# robot_board.net
KiCad netlist of a schematic drawn in EAGLE
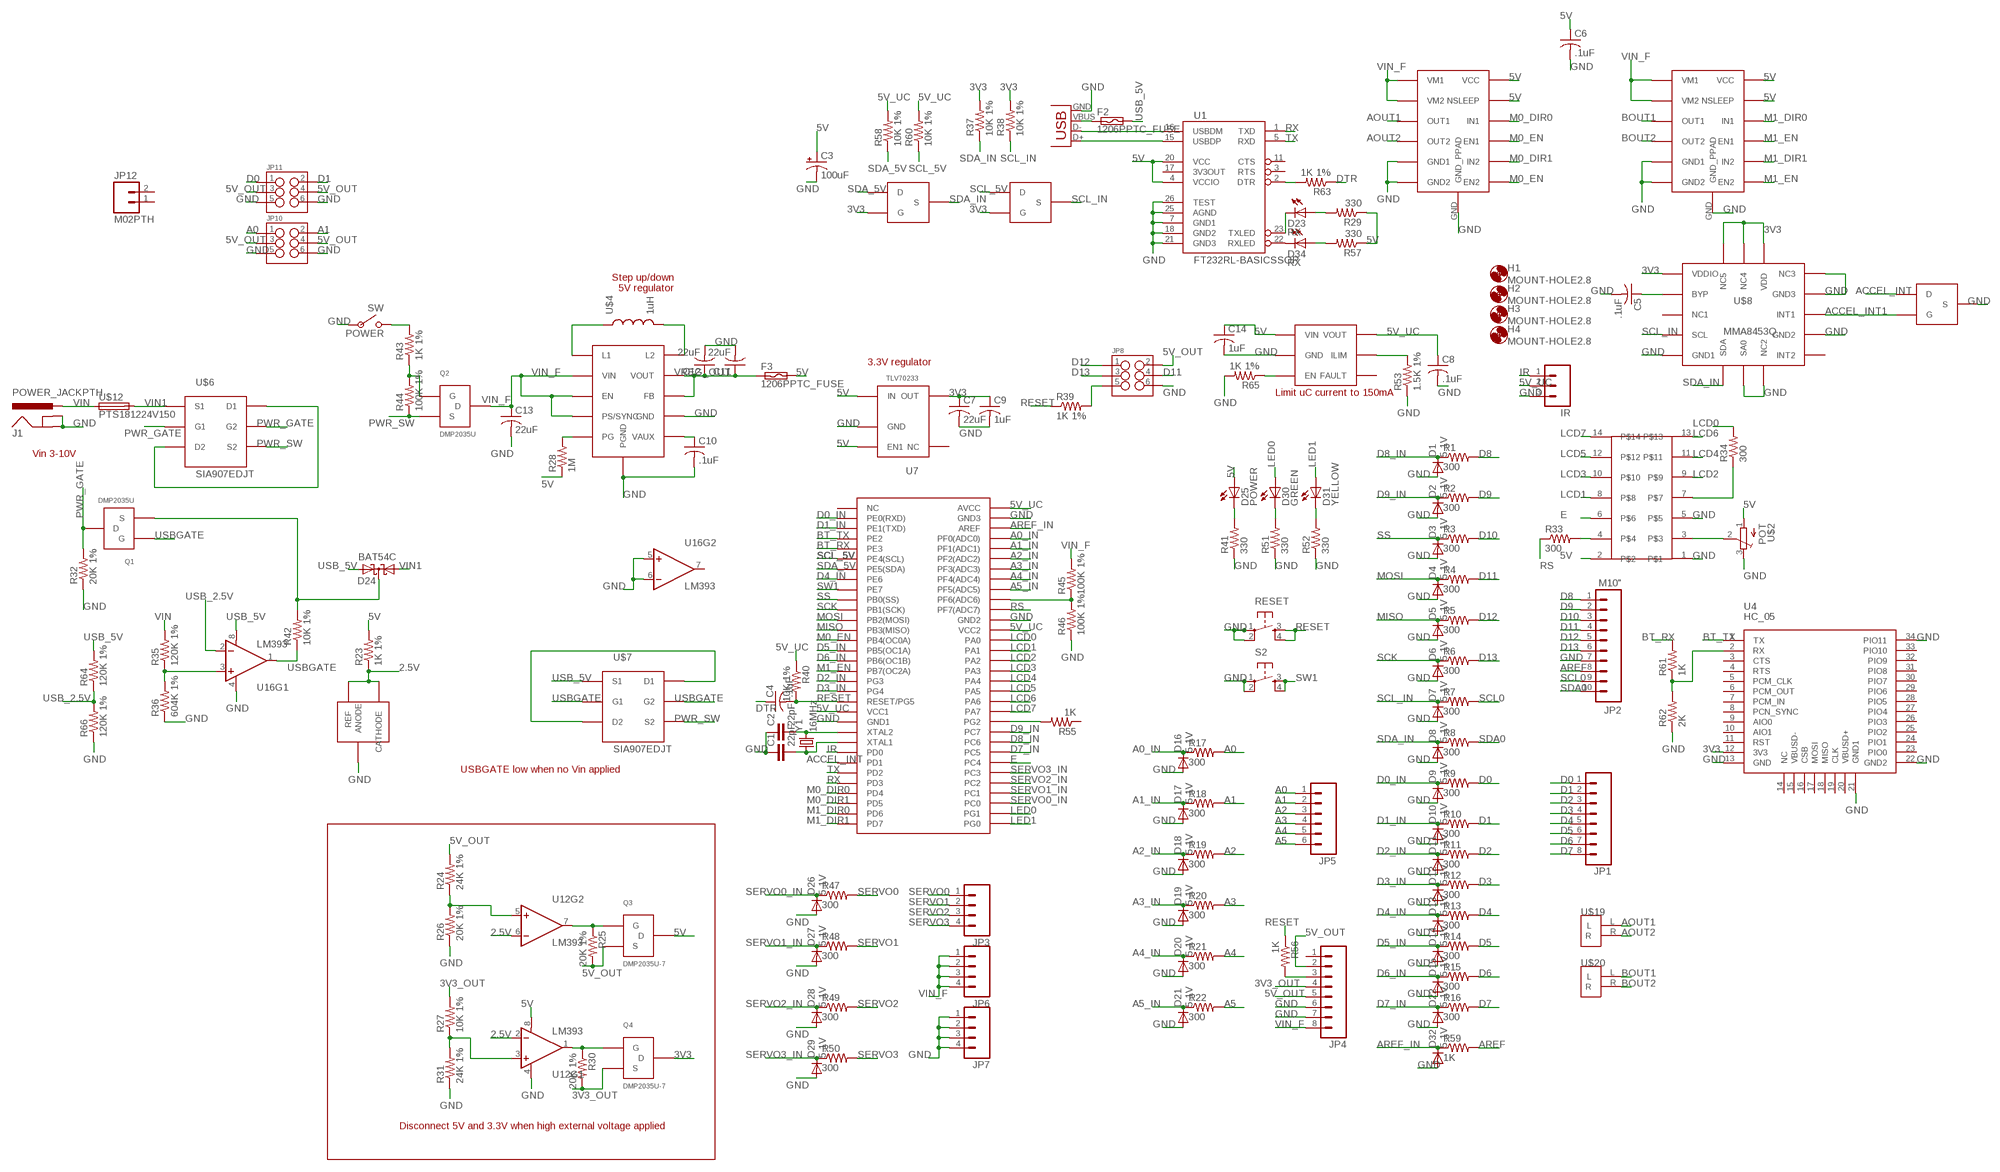
[diagram p0: schematic, sheet 1]

(export (version "E")
  (design (tool "Eeschema 10.0.6"))
  (components
    (comp (ref "C1")
      (value "22pF")
      (footprint "eagle-import:0805")
      (libsource (lib "eagle-import") (part "CAP0805"))
    )
    (comp (ref "C2")
      (value "22pF")
      (footprint "eagle-import:0805")
      (libsource (lib "eagle-import") (part "CAP0805"))
    )
    (comp (ref "C3")
      (value "100uF")
      (footprint "eagle-import:PANASONIC_D")
      (libsource (lib "eagle-import") (part "CAP_POLD"))
    )
    (comp (ref "C4")
      (value ".1uF")
      (footprint "eagle-import:C1206")
      (libsource (lib "eagle-import") (part "C-USC1206"))
    )
    (comp (ref "C5")
      (value ".1uF")
      (footprint "eagle-import:C1206")
      (libsource (lib "eagle-import") (part "C-USC1206"))
    )
    (comp (ref "C6")
      (value ".1uF")
      (footprint "eagle-import:C1206")
      (libsource (lib "eagle-import") (part "C-USC1206"))
    )
    (comp (ref "C7")
      (value "22uF")
      (footprint "eagle-import:C1206")
      (libsource (lib "eagle-import") (part "C-USC1206"))
    )
    (comp (ref "C8")
      (value ".1uF")
      (footprint "eagle-import:C1206")
      (libsource (lib "eagle-import") (part "C-USC1206"))
    )
    (comp (ref "C9")
      (value "1uF")
      (footprint "eagle-import:C1206")
      (libsource (lib "eagle-import") (part "C-USC1206"))
    )
    (comp (ref "C10")
      (value ".1uF")
      (footprint "eagle-import:C1206")
      (libsource (lib "eagle-import") (part "C-USC1206"))
    )
    (comp (ref "C11")
      (value "22uF")
      (footprint "eagle-import:C1206")
      (libsource (lib "eagle-import") (part "C-USC1206"))
    )
    (comp (ref "C12")
      (value "22uF")
      (footprint "eagle-import:C1206")
      (libsource (lib "eagle-import") (part "C-USC1206"))
    )
    (comp (ref "C13")
      (value "22uF")
      (footprint "eagle-import:C1206")
      (libsource (lib "eagle-import") (part "C-USC1206"))
    )
    (comp (ref "C14")
      (value "1uF")
      (footprint "eagle-import:C1206")
      (libsource (lib "eagle-import") (part "C-USC1206"))
    )
    (comp (ref "D1")
      (value "5.1V")
      (footprint "eagle-import:SOT23-3")
      (libsource (lib "eagle-import") (part "DIODESOT23"))
    )
    (comp (ref "D2")
      (value "5.1V")
      (footprint "eagle-import:SOT23-3")
      (libsource (lib "eagle-import") (part "DIODESOT23"))
    )
    (comp (ref "D3")
      (value "5.1V")
      (footprint "eagle-import:SOT23-3")
      (libsource (lib "eagle-import") (part "DIODESOT23"))
    )
    (comp (ref "D4")
      (value "5.1V")
      (footprint "eagle-import:SOT23-3")
      (libsource (lib "eagle-import") (part "DIODESOT23"))
    )
    (comp (ref "D5")
      (value "5.1V")
      (footprint "eagle-import:SOT23-3")
      (libsource (lib "eagle-import") (part "DIODESOT23"))
    )
    (comp (ref "D6")
      (value "5.1V")
      (footprint "eagle-import:SOT23-3")
      (libsource (lib "eagle-import") (part "DIODESOT23"))
    )
    (comp (ref "D7")
      (value "5.1V")
      (footprint "eagle-import:SOT23-3")
      (libsource (lib "eagle-import") (part "DIODESOT23"))
    )
    (comp (ref "D8")
      (value "5.1V")
      (footprint "eagle-import:SOT23-3")
      (libsource (lib "eagle-import") (part "DIODESOT23"))
    )
    (comp (ref "D9")
      (value "5.1V")
      (footprint "eagle-import:SOT23-3")
      (libsource (lib "eagle-import") (part "DIODESOT23"))
    )
    (comp (ref "D10")
      (value "5.1V")
      (footprint "eagle-import:SOT23-3")
      (libsource (lib "eagle-import") (part "DIODESOT23"))
    )
    (comp (ref "D11")
      (value "5.1V")
      (footprint "eagle-import:SOT23-3")
      (libsource (lib "eagle-import") (part "DIODESOT23"))
    )
    (comp (ref "D12")
      (value "5.1V")
      (footprint "eagle-import:SOT23-3")
      (libsource (lib "eagle-import") (part "DIODESOT23"))
    )
    (comp (ref "D13")
      (value "5.1V")
      (footprint "eagle-import:SOT23-3")
      (libsource (lib "eagle-import") (part "DIODESOT23"))
    )
    (comp (ref "D14")
      (value "5.1V")
      (footprint "eagle-import:SOT23-3")
      (libsource (lib "eagle-import") (part "DIODESOT23"))
    )
    (comp (ref "D15")
      (value "5.1V")
      (footprint "eagle-import:SOT23-3")
      (libsource (lib "eagle-import") (part "DIODESOT23"))
    )
    (comp (ref "D16")
      (value "5.1V")
      (footprint "eagle-import:SOT23-3")
      (libsource (lib "eagle-import") (part "DIODESOT23"))
    )
    (comp (ref "D17")
      (value "5.1V")
      (footprint "eagle-import:SOT23-3")
      (libsource (lib "eagle-import") (part "DIODESOT23"))
    )
    (comp (ref "D18")
      (value "5.1V")
      (footprint "eagle-import:SOT23-3")
      (libsource (lib "eagle-import") (part "DIODESOT23"))
    )
    (comp (ref "D19")
      (value "5.1V")
      (footprint "eagle-import:SOT23-3")
      (libsource (lib "eagle-import") (part "DIODESOT23"))
    )
    (comp (ref "D20")
      (value "5.1V")
      (footprint "eagle-import:SOT23-3")
      (libsource (lib "eagle-import") (part "DIODESOT23"))
    )
    (comp (ref "D21")
      (value "5.1V")
      (footprint "eagle-import:SOT23-3")
      (libsource (lib "eagle-import") (part "DIODESOT23"))
    )
    (comp (ref "D22")
      (value "5.1V")
      (footprint "eagle-import:SOT23-3")
      (libsource (lib "eagle-import") (part "DIODESOT23"))
    )
    (comp (ref "D23")
      (value "RX")
      (footprint "eagle-import:LED-1206")
      (libsource (lib "eagle-import") (part "LED-GREENLILYPAD"))
    )
    (comp (ref "D24")
      (value "BAT54C")
      (footprint "eagle-import:SOT23")
      (libsource (lib "eagle-import") (part "BAT54C"))
    )
    (comp (ref "D25")
      (value "POWER")
      (footprint "eagle-import:LED-1206")
      (libsource (lib "eagle-import") (part "LED-GREENLILYPAD"))
    )
    (comp (ref "D26")
      (value "5.1V")
      (footprint "eagle-import:SOT23-3")
      (libsource (lib "eagle-import") (part "DIODESOT23"))
    )
    (comp (ref "D27")
      (value "5.1V")
      (footprint "eagle-import:SOT23-3")
      (libsource (lib "eagle-import") (part "DIODESOT23"))
    )
    (comp (ref "D28")
      (value "5.1V")
      (footprint "eagle-import:SOT23-3")
      (libsource (lib "eagle-import") (part "DIODESOT23"))
    )
    (comp (ref "D29")
      (value "5.1V")
      (footprint "eagle-import:SOT23-3")
      (libsource (lib "eagle-import") (part "DIODESOT23"))
    )
    (comp (ref "D30")
      (value "GREEN")
      (footprint "eagle-import:LED-1206")
      (libsource (lib "eagle-import") (part "LED-GREENLILYPAD"))
    )
    (comp (ref "D31")
      (value "YELLOW")
      (footprint "eagle-import:LED-1206")
      (libsource (lib "eagle-import") (part "LED-GREENLILYPAD"))
    )
    (comp (ref "D32")
      (value "5.1V")
      (footprint "eagle-import:SOT23-3")
      (libsource (lib "eagle-import") (part "DIODESOT23"))
    )
    (comp (ref "D34")
      (value "RX")
      (footprint "eagle-import:LED-1206")
      (libsource (lib "eagle-import") (part "LED-GREENLILYPAD"))
    )
    (comp (ref "F2")
      (value "1206PPTC_FUSE")
      (footprint "eagle-import:R1206")
      (libsource (lib "eagle-import") (part "1206PPTC_FUSE"))
    )
    (comp (ref "F3")
      (value "1206PPTC_FUSE")
      (footprint "eagle-import:R1206")
      (libsource (lib "eagle-import") (part "1206PPTC_FUSE"))
    )
    (comp (ref "H1")
      (value "MOUNT-HOLE2.8")
      (footprint "eagle-import:2,8")
      (libsource (lib "eagle-import") (part "MOUNT-HOLE2.8"))
    )
    (comp (ref "H2")
      (value "MOUNT-HOLE2.8")
      (footprint "eagle-import:2,8")
      (libsource (lib "eagle-import") (part "MOUNT-HOLE2.8"))
    )
    (comp (ref "H3")
      (value "MOUNT-HOLE2.8")
      (footprint "eagle-import:2,8")
      (libsource (lib "eagle-import") (part "MOUNT-HOLE2.8"))
    )
    (comp (ref "H4")
      (value "MOUNT-HOLE2.8")
      (footprint "eagle-import:2,8")
      (libsource (lib "eagle-import") (part "MOUNT-HOLE2.8"))
    )
    (comp (ref "IR")
      (value "M03PTH")
      (footprint "eagle-import:1X03")
      (libsource (lib "eagle-import") (part "M03PTH"))
    )
    (comp (ref "J1")
      (value "POWER_JACKPTH")
      (footprint "eagle-import:POWER_JACK_PTH")
      (libsource (lib "eagle-import") (part "POWER_JACKPTH"))
    )
    (comp (ref "JP1")
      (value "M081X08")
      (footprint "eagle-import:1X08")
      (libsource (lib "eagle-import") (part "M081X08"))
    )
    (comp (ref "JP2")
      (value "M10\"")
      (footprint "eagle-import:1X10")
      (libsource (lib "eagle-import") (part "M10{dblquote}"))
    )
    (comp (ref "JP3")
      (value "M04PTH")
      (footprint "eagle-import:1X04")
      (libsource (lib "eagle-import") (part "M04PTH"))
    )
    (comp (ref "JP4")
      (value "M081X08")
      (footprint "eagle-import:1X08")
      (libsource (lib "eagle-import") (part "M081X08"))
    )
    (comp (ref "JP5")
      (value "M06SIP")
      (footprint "eagle-import:1X06")
      (libsource (lib "eagle-import") (part "M06SIP"))
    )
    (comp (ref "JP6")
      (value "M04PTH")
      (footprint "eagle-import:1X04")
      (libsource (lib "eagle-import") (part "M04PTH"))
    )
    (comp (ref "JP7")
      (value "M04PTH")
      (footprint "eagle-import:1X04")
      (libsource (lib "eagle-import") (part "M04PTH"))
    )
    (comp (ref "JP8")
      (value "M03X22X3_SILK_SM")
      (footprint "eagle-import:2X3")
      (libsource (lib "eagle-import") (part "M03X22X3_SILK_SM"))
    )
    (comp (ref "JP9")
      (value "USB-B")
      (footprint "eagle-import:USB-B-PTH")
      (libsource (lib "eagle-import") (part "USBPTH"))
    )
    (comp (ref "JP10")
      (value "M03X22X3_SILK_SM")
      (footprint "eagle-import:2X3")
      (libsource (lib "eagle-import") (part "M03X22X3_SILK_SM"))
    )
    (comp (ref "JP11")
      (value "M03X22X3_SILK_SM")
      (footprint "eagle-import:2X3")
      (libsource (lib "eagle-import") (part "M03X22X3_SILK_SM"))
    )
    (comp (ref "JP12")
      (value "M02PTH")
      (footprint "eagle-import:1X02")
      (libsource (lib "eagle-import") (part "M02PTH"))
    )
    (comp (ref "POWER")
      (value "SW")
      (footprint "eagle-import:SW")
      (libsource (lib "eagle-import") (part "SW"))
    )
    (comp (ref "Q1")
      (value "DMP2035U")
      (footprint "eagle-import:SOT23")
      (libsource (lib "eagle-import") (part "DMP2035U"))
    )
    (comp (ref "Q2")
      (value "DMP2035U")
      (footprint "eagle-import:SOT23")
      (libsource (lib "eagle-import") (part "DMP2035U"))
    )
    (comp (ref "Q3")
      (value "DMP2035U-7")
      (footprint "eagle-import:SOT23@1")
      (libsource (lib "eagle-import") (part "DMP2035U-7"))
    )
    (comp (ref "Q4")
      (value "DMP2035U-7")
      (footprint "eagle-import:SOT23@1")
      (libsource (lib "eagle-import") (part "DMP2035U-7"))
    )
    (comp (ref "R1")
      (value "300")
      (footprint "eagle-import:R1206")
      (libsource (lib "eagle-import") (part "R-US_R1206"))
    )
    (comp (ref "R2")
      (value "300")
      (footprint "eagle-import:R1206")
      (libsource (lib "eagle-import") (part "R-US_R1206"))
    )
    (comp (ref "R3")
      (value "300")
      (footprint "eagle-import:R1206")
      (libsource (lib "eagle-import") (part "R-US_R1206"))
    )
    (comp (ref "R4")
      (value "300")
      (footprint "eagle-import:R1206")
      (libsource (lib "eagle-import") (part "R-US_R1206"))
    )
    (comp (ref "R5")
      (value "300")
      (footprint "eagle-import:R1206")
      (libsource (lib "eagle-import") (part "R-US_R1206"))
    )
    (comp (ref "R6")
      (value "300")
      (footprint "eagle-import:R1206")
      (libsource (lib "eagle-import") (part "R-US_R1206"))
    )
    (comp (ref "R7")
      (value "300")
      (footprint "eagle-import:R1206")
      (libsource (lib "eagle-import") (part "R-US_R1206"))
    )
    (comp (ref "R8")
      (value "300")
      (footprint "eagle-import:R1206")
      (libsource (lib "eagle-import") (part "R-US_R1206"))
    )
    (comp (ref "R9")
      (value "300")
      (footprint "eagle-import:R1206")
      (libsource (lib "eagle-import") (part "R-US_R1206"))
    )
    (comp (ref "R10")
      (value "300")
      (footprint "eagle-import:R1206")
      (libsource (lib "eagle-import") (part "R-US_R1206"))
    )
    (comp (ref "R11")
      (value "300")
      (footprint "eagle-import:R1206")
      (libsource (lib "eagle-import") (part "R-US_R1206"))
    )
    (comp (ref "R12")
      (value "300")
      (footprint "eagle-import:R1206")
      (libsource (lib "eagle-import") (part "R-US_R1206"))
    )
    (comp (ref "R13")
      (value "300")
      (footprint "eagle-import:R1206")
      (libsource (lib "eagle-import") (part "R-US_R1206"))
    )
    (comp (ref "R14")
      (value "300")
      (footprint "eagle-import:R1206")
      (libsource (lib "eagle-import") (part "R-US_R1206"))
    )
    (comp (ref "R15")
      (value "300")
      (footprint "eagle-import:R1206")
      (libsource (lib "eagle-import") (part "R-US_R1206"))
    )
    (comp (ref "R16")
      (value "300")
      (footprint "eagle-import:R1206")
      (libsource (lib "eagle-import") (part "R-US_R1206"))
    )
    (comp (ref "R17")
      (value "300")
      (footprint "eagle-import:R1206")
      (libsource (lib "eagle-import") (part "R-US_R1206"))
    )
    (comp (ref "R18")
      (value "300")
      (footprint "eagle-import:R1206")
      (libsource (lib "eagle-import") (part "R-US_R1206"))
    )
    (comp (ref "R19")
      (value "300")
      (footprint "eagle-import:R1206")
      (libsource (lib "eagle-import") (part "R-US_R1206"))
    )
    (comp (ref "R20")
      (value "300")
      (footprint "eagle-import:R1206")
      (libsource (lib "eagle-import") (part "R-US_R1206"))
    )
    (comp (ref "R21")
      (value "300")
      (footprint "eagle-import:R1206")
      (libsource (lib "eagle-import") (part "R-US_R1206"))
    )
    (comp (ref "R22")
      (value "300")
      (footprint "eagle-import:R1206")
      (libsource (lib "eagle-import") (part "R-US_R1206"))
    )
    (comp (ref "R23")
      (value "1K 1%")
      (footprint "eagle-import:R1206")
      (libsource (lib "eagle-import") (part "R-US_R1206"))
    )
    (comp (ref "R24")
      (value "24K 1%")
      (footprint "eagle-import:R1206")
      (libsource (lib "eagle-import") (part "R-US_R1206"))
    )
    (comp (ref "R25")
      (value "20K 1%")
      (footprint "eagle-import:R1206")
      (libsource (lib "eagle-import") (part "R-US_R1206"))
    )
    (comp (ref "R26")
      (value "20K 1%")
      (footprint "eagle-import:R1206")
      (libsource (lib "eagle-import") (part "R-US_R1206"))
    )
    (comp (ref "R27")
      (value "10K 1%")
      (footprint "eagle-import:R1206")
      (libsource (lib "eagle-import") (part "R-US_R1206"))
    )
    (comp (ref "R28")
      (value "1M")
      (footprint "eagle-import:R1206")
      (libsource (lib "eagle-import") (part "R-US_R1206"))
    )
    (comp (ref "R29")
      (value "330")
      (footprint "eagle-import:R1206")
      (libsource (lib "eagle-import") (part "R-US_R1206"))
    )
    (comp (ref "R30")
      (value "20K 1%")
      (footprint "eagle-import:R1206")
      (libsource (lib "eagle-import") (part "R-US_R1206"))
    )
    (comp (ref "R31")
      (value "24K 1%")
      (footprint "eagle-import:R1206")
      (libsource (lib "eagle-import") (part "R-US_R1206"))
    )
    (comp (ref "R32")
      (value "20K 1%")
      (footprint "eagle-import:R1206")
      (libsource (lib "eagle-import") (part "R-US_R1206"))
    )
    (comp (ref "R33")
      (value "300")
      (footprint "eagle-import:R1206")
      (libsource (lib "eagle-import") (part "R-US_R1206"))
    )
    (comp (ref "R34")
      (value "300")
      (footprint "eagle-import:R1206")
      (libsource (lib "eagle-import") (part "R-US_R1206"))
    )
    (comp (ref "R35")
      (value "120K 1%")
      (footprint "eagle-import:R1206")
      (libsource (lib "eagle-import") (part "R-US_R1206"))
    )
    (comp (ref "R36")
      (value "604K 1%")
      (footprint "eagle-import:R1206")
      (libsource (lib "eagle-import") (part "R-US_R1206"))
    )
    (comp (ref "R37")
      (value "10K 1%")
      (footprint "eagle-import:R1206")
      (libsource (lib "eagle-import") (part "R-US_R1206"))
    )
    (comp (ref "R38")
      (value "10K 1%")
      (footprint "eagle-import:R1206")
      (libsource (lib "eagle-import") (part "R-US_R1206"))
    )
    (comp (ref "R39")
      (value "1K 1%")
      (footprint "eagle-import:R1206")
      (libsource (lib "eagle-import") (part "R-US_R1206"))
    )
    (comp (ref "R40")
      (value "10K 1%")
      (footprint "eagle-import:R1206")
      (libsource (lib "eagle-import") (part "R-US_R1206"))
    )
    (comp (ref "R41")
      (value "330")
      (footprint "eagle-import:R1206")
      (libsource (lib "eagle-import") (part "R-US_R1206"))
    )
    (comp (ref "R42")
      (value "10K 1%")
      (footprint "eagle-import:R1206")
      (libsource (lib "eagle-import") (part "R-US_R1206"))
    )
    (comp (ref "R43")
      (value "1K 1%")
      (footprint "eagle-import:R1206")
      (libsource (lib "eagle-import") (part "R-US_R1206"))
    )
    (comp (ref "R44")
      (value "100K 1%")
      (footprint "eagle-import:R1206")
      (libsource (lib "eagle-import") (part "R-US_R1206"))
    )
    (comp (ref "R45")
      (value "100K 1%")
      (footprint "eagle-import:R1206")
      (libsource (lib "eagle-import") (part "R-US_R1206"))
    )
    (comp (ref "R46")
      (value "100K 1%")
      (footprint "eagle-import:R1206")
      (libsource (lib "eagle-import") (part "R-US_R1206"))
    )
    (comp (ref "R47")
      (value "300")
      (footprint "eagle-import:R1206")
      (libsource (lib "eagle-import") (part "R-US_R1206"))
    )
    (comp (ref "R48")
      (value "300")
      (footprint "eagle-import:R1206")
      (libsource (lib "eagle-import") (part "R-US_R1206"))
    )
    (comp (ref "R49")
      (value "300")
      (footprint "eagle-import:R1206")
      (libsource (lib "eagle-import") (part "R-US_R1206"))
    )
    (comp (ref "R50")
      (value "300")
      (footprint "eagle-import:R1206")
      (libsource (lib "eagle-import") (part "R-US_R1206"))
    )
    (comp (ref "R51")
      (value "330")
      (footprint "eagle-import:R1206")
      (libsource (lib "eagle-import") (part "R-US_R1206"))
    )
    (comp (ref "R52")
      (value "330")
      (footprint "eagle-import:R1206")
      (libsource (lib "eagle-import") (part "R-US_R1206"))
    )
    (comp (ref "R53")
      (value "1.5K 1%")
      (footprint "eagle-import:R1206")
      (libsource (lib "eagle-import") (part "R-US_R1206"))
    )
    (comp (ref "R55")
      (value "1K")
      (footprint "eagle-import:R1206")
      (libsource (lib "eagle-import") (part "R-US_R1206"))
    )
    (comp (ref "R56")
      (value "1K")
      (footprint "eagle-import:R1206")
      (libsource (lib "eagle-import") (part "R-US_R1206"))
    )
    (comp (ref "R57")
      (value "330")
      (footprint "eagle-import:R1206")
      (libsource (lib "eagle-import") (part "R-US_R1206"))
    )
    (comp (ref "R58")
      (value "10K 1%")
      (footprint "eagle-import:R1206")
      (libsource (lib "eagle-import") (part "R-US_R1206"))
    )
    (comp (ref "R59")
      (value "1K")
      (footprint "eagle-import:R1206")
      (libsource (lib "eagle-import") (part "R-US_R1206"))
    )
    (comp (ref "R60")
      (value "10K 1%")
      (footprint "eagle-import:R1206")
      (libsource (lib "eagle-import") (part "R-US_R1206"))
    )
    (comp (ref "R61")
      (value "1K")
      (footprint "eagle-import:R1206")
      (libsource (lib "eagle-import") (part "R-US_R1206"))
    )
    (comp (ref "R62")
      (value "2K")
      (footprint "eagle-import:R1206")
      (libsource (lib "eagle-import") (part "R-US_R1206"))
    )
    (comp (ref "R63")
      (value "1K 1%")
      (footprint "eagle-import:R1206")
      (libsource (lib "eagle-import") (part "R-US_R1206"))
    )
    (comp (ref "R64")
      (value "120K 1%")
      (footprint "eagle-import:R1206")
      (libsource (lib "eagle-import") (part "R-US_R1206"))
    )
    (comp (ref "R65")
      (value "1K 1%")
      (footprint "eagle-import:R1206")
      (libsource (lib "eagle-import") (part "R-US_R1206"))
    )
    (comp (ref "R66")
      (value "120K 1%")
      (footprint "eagle-import:R1206")
      (libsource (lib "eagle-import") (part "R-US_R1206"))
    )
    (comp (ref "RESET")
      (value "TAC_SWITCHPTH")
      (footprint "eagle-import:TACTILE-PTH")
      (libsource (lib "eagle-import") (part "TAC_SWITCHPTH"))
    )
    (comp (ref "S2")
      (value "TAC_SWITCHPTH")
      (footprint "eagle-import:TACTILE-PTH")
      (libsource (lib "eagle-import") (part "TAC_SWITCHPTH"))
    )
    (comp (ref "U$1")
      (value "2X7HEADER")
      (footprint "eagle-import:2X7")
      (libsource (lib "eagle-import") (part "2X7HEADER"))
    )
    (comp (ref "U$2")
      (value "POT")
      (footprint "eagle-import:POT")
      (libsource (lib "eagle-import") (part "POT"))
    )
    (comp (ref "U$3")
      (value "TPS63061")
      (footprint "eagle-import:WSON-10")
      (libsource (lib "eagle-import") (part "TPS63061"))
    )
    (comp (ref "U$4")
      (value "1uH")
      (footprint "eagle-import:TAIYO4012")
      (libsource (lib "eagle-import") (part "TAIYO4012"))
    )
    (comp (ref "U$5")
      (value "AP431SAG-7")
      (footprint "eagle-import:SOT23")
      (libsource (lib "eagle-import") (part "AP431SAG-7"))
    )
    (comp (ref "U$6")
      (value "SIA907EDJT")
      (footprint "eagle-import:SC70T")
      (libsource (lib "eagle-import") (part "SIA907EDJT"))
    )
    (comp (ref "U$7")
      (value "SIA907EDJT")
      (footprint "eagle-import:SC70T")
      (libsource (lib "eagle-import") (part "SIA907EDJT"))
    )
    (comp (ref "U$8")
      (value "MMA8453Q")
      (footprint "eagle-import:QFN-COL")
      (libsource (lib "eagle-import") (part "MMA8453Q"))
    )
    (comp (ref "U$9")
      (value "BSS138")
      (footprint "eagle-import:SOT23")
      (libsource (lib "eagle-import") (part "BSS138"))
    )
    (comp (ref "U$10")
      (value "BSS138")
      (footprint "eagle-import:SOT23")
      (libsource (lib "eagle-import") (part "BSS138"))
    )
    (comp (ref "U$11")
      (value "BSS138")
      (footprint "eagle-import:SOT23")
      (libsource (lib "eagle-import") (part "BSS138"))
    )
    (comp (ref "U$12")
      (value "PTS181224V150")
      (footprint "eagle-import:C1812")
      (libsource (lib "eagle-import") (part "PTS181224V150"))
    )
    (comp (ref "U$19")
      (value "2POS_TERMINAL")
      (footprint "eagle-import:2POS_TERMINAL")
      (libsource (lib "eagle-import") (part "2POS_TERMINAL"))
    )
    (comp (ref "U$20")
      (value "2POS_TERMINAL")
      (footprint "eagle-import:2POS_TERMINAL")
      (libsource (lib "eagle-import") (part "2POS_TERMINAL"))
    )
    (comp (ref "U1")
      (value "FT232RL-BASICSSOP")
      (footprint "eagle-import:SSOP28DB")
      (libsource (lib "eagle-import") (part "FT232RL-BASICSSOP"))
    )
    (comp (ref "U4")
      (value "HC_05")
      (footprint "eagle-import:BLUETOOTH_SMD")
      (libsource (lib "eagle-import") (part "HC_05"))
    )
    (comp (ref "U7")
      (value "TLV70233")
      (footprint "eagle-import:SOT-23-5")
      (libsource (lib "eagle-import") (part "TLV70233"))
    )
    (comp (ref "U8")
      (value "MIC2009A")
      (footprint "eagle-import:SOT23-M5")
      (libsource (lib "eagle-import") (part "MIC2009A"))
    )
    (comp (ref "U9")
      (value "DRV8839")
      (footprint "eagle-import:PWSON-N12")
      (libsource (lib "eagle-import") (part "DRV8839"))
    )
    (comp (ref "U10")
      (value "DRV8839")
      (footprint "eagle-import:PWSON-N12")
      (libsource (lib "eagle-import") (part "DRV8839"))
    )
    (comp (ref "U12")
      (value "LM393")
      (footprint "eagle-import:SO08")
      (libsource (lib "eagle-import") (part "LM393"))
    )
    (comp (ref "U16")
      (value "LM393")
      (footprint "eagle-import:SO08")
      (libsource (lib "eagle-import") (part "LM393"))
    )
    (comp (ref "U17")
      (value "ATMEGA325PA")
      (footprint "eagle-import:TQFP64")
      (libsource (lib "eagle-import") (part "ATMEGA325PA"))
    )
    (comp (ref "Y1")
      (value "16MHz")
      (footprint "eagle-import:CRYSTAL-SMD-10.5X4.8-2PIN")
      (libsource (lib "eagle-import") (part "CRYSTAL10.5X4.8"))
    )
  )
  (nets
    (net (code "1") (name "/2.5V") (class "Default")
      (node (ref "R23") (pin "1") (pinfunction "1_1") (pintype "passive"))
      (node (ref "U$5") (pin "1") (pinfunction "CATHODE_1") (pintype "bidirectional"))
      (node (ref "U$5") (pin "2") (pinfunction "REF_2") (pintype "bidirectional"))
      (node (ref "U12") (pin "2") (pinfunction "-IN_2") (pintype "input"))
      (node (ref "U12") (pin "6") (pinfunction "-IN_6") (pintype "input"))
    )
    (net (code "2") (name "/3V3") (class "Default")
      (node (ref "C7") (pin "1") (pinfunction "1_1") (pintype "passive"))
      (node (ref "C9") (pin "1") (pinfunction "1_1") (pintype "passive"))
      (node (ref "Q4") (pin "3") (pinfunction "D_3") (pintype "bidirectional"))
      (node (ref "R37") (pin "2") (pinfunction "2_2") (pintype "passive"))
      (node (ref "R38") (pin "2") (pinfunction "2_2") (pintype "passive"))
      (node (ref "U$10") (pin "1") (pinfunction "G_1") (pintype "bidirectional"))
      (node (ref "U$8") (pin "P$1") (pinfunction "VDDIO_P$1") (pintype "bidirectional"))
      (node (ref "U$8") (pin "P$14") (pinfunction "VDD_P$14") (pintype "bidirectional"))
      (node (ref "U$8") (pin "P$15") (pinfunction "NC4_P$15") (pintype "bidirectional"))
      (node (ref "U$8") (pin "P$16") (pinfunction "NC5_P$16") (pintype "bidirectional"))
      (node (ref "U$9") (pin "1") (pinfunction "G_1") (pintype "bidirectional"))
      (node (ref "U4") (pin "12") (pinfunction "3V3_12") (pintype "bidirectional"))
      (node (ref "U7") (pin "P$4") (pinfunction "OUT_P$4") (pintype "bidirectional"))
    )
    (net (code "3") (name "/3V3_OUT") (class "Default")
      (node (ref "JP4") (pin "4") (pinfunction "4_4") (pintype "passive"))
      (node (ref "Q4") (pin "2") (pinfunction "S_2") (pintype "bidirectional"))
      (node (ref "R27") (pin "2") (pinfunction "2_2") (pintype "passive"))
      (node (ref "R30") (pin "2") (pinfunction "2_2") (pintype "passive"))
    )
    (net (code "4") (name "/5V") (class "Default")
      (node (ref "C14") (pin "1") (pinfunction "1_1") (pintype "passive"))
      (node (ref "C3") (pin "+") (pinfunction "+_+") (pintype "passive"))
      (node (ref "C6") (pin "1") (pinfunction "1_1") (pintype "passive"))
      (node (ref "D25") (pin "A") (pinfunction "A_A") (pintype "passive"))
      (node (ref "F3") (pin "2") (pinfunction "2_2") (pintype "passive"))
      (node (ref "Q3") (pin "3") (pinfunction "D_3") (pintype "bidirectional"))
      (node (ref "R23") (pin "2") (pinfunction "2_2") (pintype "passive"))
      (node (ref "R28") (pin "1") (pinfunction "1_1") (pintype "passive"))
      (node (ref "R29") (pin "1") (pinfunction "1_1") (pintype "passive"))
      (node (ref "R57") (pin "1") (pinfunction "1_1") (pintype "passive"))
      (node (ref "U$1") (pin "2") (pinfunction "P$2_2") (pintype "bidirectional"))
      (node (ref "U$2") (pin "1") (pinfunction "A_1") (pintype "passive"))
      (node (ref "U1") (pin "20") (pinfunction "VCC_20") (pintype "power_in"))
      (node (ref "U1") (pin "4") (pinfunction "VCCIO_4") (pintype "power_in"))
      (node (ref "U10") (pin "P$7") (pinfunction "VCC_P$7") (pintype "bidirectional"))
      (node (ref "U10") (pin "P$8") (pinfunction "NSLEEP_P$8") (pintype "bidirectional"))
      (node (ref "U12") (pin "8") (pinfunction "V+_8") (pintype "power_in"))
      (node (ref "U7") (pin "P$1") (pinfunction "IN_P$1") (pintype "bidirectional"))
      (node (ref "U7") (pin "P$3") (pinfunction "EN1_P$3") (pintype "bidirectional"))
      (node (ref "U8") (pin "P$1") (pinfunction "VIN_P$1") (pintype "bidirectional"))
      (node (ref "U9") (pin "P$7") (pinfunction "VCC_P$7") (pintype "bidirectional"))
      (node (ref "U9") (pin "P$8") (pinfunction "NSLEEP_P$8") (pintype "bidirectional"))
    )
    (net (code "5") (name "/5V_OUT") (class "Default")
      (node (ref "JP10") (pin "3") (pinfunction "3_3") (pintype "bidirectional"))
      (node (ref "JP10") (pin "4") (pinfunction "4_4") (pintype "bidirectional"))
      (node (ref "JP11") (pin "3") (pinfunction "3_3") (pintype "bidirectional"))
      (node (ref "JP11") (pin "4") (pinfunction "4_4") (pintype "bidirectional"))
      (node (ref "JP4") (pin "2") (pinfunction "2_2") (pintype "passive"))
      (node (ref "JP4") (pin "5") (pinfunction "5_5") (pintype "passive"))
      (node (ref "JP8") (pin "2") (pinfunction "2_2") (pintype "bidirectional"))
      (node (ref "Q3") (pin "2") (pinfunction "S_2") (pintype "bidirectional"))
      (node (ref "R24") (pin "2") (pinfunction "2_2") (pintype "passive"))
      (node (ref "R25") (pin "2") (pinfunction "2_2") (pintype "passive"))
    )
    (net (code "6") (name "/5V_UC") (class "Default")
      (node (ref "C8") (pin "1") (pinfunction "1_1") (pintype "passive"))
      (node (ref "IR") (pin "2") (pinfunction "2_2") (pintype "passive"))
      (node (ref "R40") (pin "1") (pinfunction "1_1") (pintype "passive"))
      (node (ref "R58") (pin "2") (pinfunction "2_2") (pintype "passive"))
      (node (ref "R60") (pin "2") (pinfunction "2_2") (pintype "passive"))
      (node (ref "U17") (pin "21") (pinfunction "VCC1_21") (pintype "bidirectional"))
      (node (ref "U17") (pin "52") (pinfunction "VCC2_52") (pintype "bidirectional"))
      (node (ref "U17") (pin "64") (pinfunction "AVCC_64") (pintype "bidirectional"))
      (node (ref "U8") (pin "P$6") (pinfunction "VOUT_P$6") (pintype "bidirectional"))
    )
    (net (code "7") (name "/A0") (class "Default")
      (node (ref "JP10") (pin "1") (pinfunction "1_1") (pintype "bidirectional"))
      (node (ref "JP5") (pin "1") (pinfunction "1_1") (pintype "passive"))
      (node (ref "R17") (pin "2") (pinfunction "2_2") (pintype "passive"))
    )
    (net (code "8") (name "/A0_IN") (class "Default")
      (node (ref "D16") (pin "3") (pinfunction "C_3") (pintype "passive"))
      (node (ref "R17") (pin "1") (pinfunction "1_1") (pintype "passive"))
      (node (ref "U17") (pin "61") (pinfunction "PF0(ADC0)_61") (pintype "bidirectional"))
    )
    (net (code "9") (name "/A1") (class "Default")
      (node (ref "JP10") (pin "2") (pinfunction "2_2") (pintype "bidirectional"))
      (node (ref "JP5") (pin "2") (pinfunction "2_2") (pintype "passive"))
      (node (ref "R18") (pin "2") (pinfunction "2_2") (pintype "passive"))
    )
    (net (code "10") (name "/A1_IN") (class "Default")
      (node (ref "D17") (pin "3") (pinfunction "C_3") (pintype "passive"))
      (node (ref "R18") (pin "1") (pinfunction "1_1") (pintype "passive"))
      (node (ref "U17") (pin "60") (pinfunction "PF1(ADC1)_60") (pintype "bidirectional"))
    )
    (net (code "11") (name "/A2") (class "Default")
      (node (ref "JP5") (pin "3") (pinfunction "3_3") (pintype "passive"))
      (node (ref "R19") (pin "2") (pinfunction "2_2") (pintype "passive"))
    )
    (net (code "12") (name "/A2_IN") (class "Default")
      (node (ref "D18") (pin "3") (pinfunction "C_3") (pintype "passive"))
      (node (ref "R19") (pin "1") (pinfunction "1_1") (pintype "passive"))
      (node (ref "U17") (pin "59") (pinfunction "PF2(ADC2)_59") (pintype "bidirectional"))
    )
    (net (code "13") (name "/A3") (class "Default")
      (node (ref "JP5") (pin "4") (pinfunction "4_4") (pintype "passive"))
      (node (ref "R20") (pin "2") (pinfunction "2_2") (pintype "passive"))
    )
    (net (code "14") (name "/A3_IN") (class "Default")
      (node (ref "D19") (pin "3") (pinfunction "C_3") (pintype "passive"))
      (node (ref "R20") (pin "1") (pinfunction "1_1") (pintype "passive"))
      (node (ref "U17") (pin "58") (pinfunction "PF3(ADC3)_58") (pintype "bidirectional"))
    )
    (net (code "15") (name "/A4") (class "Default")
      (node (ref "JP5") (pin "5") (pinfunction "5_5") (pintype "passive"))
      (node (ref "R21") (pin "2") (pinfunction "2_2") (pintype "passive"))
    )
    (net (code "16") (name "/A4_IN") (class "Default")
      (node (ref "D20") (pin "3") (pinfunction "C_3") (pintype "passive"))
      (node (ref "R21") (pin "1") (pinfunction "1_1") (pintype "passive"))
      (node (ref "U17") (pin "57") (pinfunction "PF4(ADC4)_57") (pintype "bidirectional"))
    )
    (net (code "17") (name "/A5") (class "Default")
      (node (ref "JP5") (pin "6") (pinfunction "6_6") (pintype "passive"))
      (node (ref "R22") (pin "2") (pinfunction "2_2") (pintype "passive"))
    )
    (net (code "18") (name "/A5_IN") (class "Default")
      (node (ref "D21") (pin "3") (pinfunction "C_3") (pintype "passive"))
      (node (ref "R22") (pin "1") (pinfunction "1_1") (pintype "passive"))
      (node (ref "U17") (pin "56") (pinfunction "PF5(ADC5)_56") (pintype "bidirectional"))
    )
    (net (code "19") (name "/ACCEL_INT") (class "Default")
      (node (ref "U$11") (pin "3") (pinfunction "D_3") (pintype "bidirectional"))
      (node (ref "U17") (pin "26") (pinfunction "PD1_26") (pintype "bidirectional"))
    )
    (net (code "20") (name "/ACCEL_INT1") (class "Default")
      (node (ref "U$11") (pin "1") (pinfunction "G_1") (pintype "bidirectional"))
      (node (ref "U$8") (pin "P$11") (pinfunction "INT1_P$11") (pintype "bidirectional"))
    )
    (net (code "21") (name "/AOUT1") (class "Default")
      (node (ref "U$19") (pin "L") (pinfunction "L_L") (pintype "bidirectional"))
      (node (ref "U9") (pin "P$3") (pinfunction "OUT1_P$3") (pintype "bidirectional"))
    )
    (net (code "22") (name "/AOUT2") (class "Default")
      (node (ref "U$19") (pin "R") (pinfunction "R_R") (pintype "bidirectional"))
      (node (ref "U9") (pin "P$4") (pinfunction "OUT2_P$4") (pintype "bidirectional"))
    )
    (net (code "23") (name "/AREF") (class "Default")
      (node (ref "JP2") (pin "8") (pinfunction "8_8") (pintype "passive"))
      (node (ref "R59") (pin "2") (pinfunction "2_2") (pintype "passive"))
    )
    (net (code "24") (name "/AREF_IN") (class "Default")
      (node (ref "D32") (pin "3") (pinfunction "C_3") (pintype "passive"))
      (node (ref "R59") (pin "1") (pinfunction "1_1") (pintype "passive"))
      (node (ref "U17") (pin "62") (pinfunction "AREF_62") (pintype "bidirectional"))
    )
    (net (code "25") (name "/BOUT1") (class "Default")
      (node (ref "U$20") (pin "L") (pinfunction "L_L") (pintype "bidirectional"))
      (node (ref "U10") (pin "P$3") (pinfunction "OUT1_P$3") (pintype "bidirectional"))
    )
    (net (code "26") (name "/BOUT2") (class "Default")
      (node (ref "U$20") (pin "R") (pinfunction "R_R") (pintype "bidirectional"))
      (node (ref "U10") (pin "P$4") (pinfunction "OUT2_P$4") (pintype "bidirectional"))
    )
    (net (code "27") (name "/BT_RX") (class "Default")
      (node (ref "R61") (pin "2") (pinfunction "2_2") (pintype "passive"))
      (node (ref "U17") (pin "5") (pinfunction "PE3_5") (pintype "bidirectional"))
    )
    (net (code "28") (name "/BT_TX") (class "Default")
      (node (ref "U17") (pin "4") (pinfunction "PE2_4") (pintype "bidirectional"))
      (node (ref "U4") (pin "1") (pinfunction "TX_1") (pintype "bidirectional"))
    )
    (net (code "29") (name "/D0") (class "Default")
      (node (ref "JP1") (pin "1") (pinfunction "1_1") (pintype "passive"))
      (node (ref "JP11") (pin "1") (pinfunction "1_1") (pintype "bidirectional"))
      (node (ref "R9") (pin "2") (pinfunction "2_2") (pintype "passive"))
    )
    (net (code "30") (name "/D0_IN") (class "Default")
      (node (ref "D9") (pin "3") (pinfunction "C_3") (pintype "passive"))
      (node (ref "R9") (pin "1") (pinfunction "1_1") (pintype "passive"))
      (node (ref "U17") (pin "2") (pinfunction "PE0(RXD)_2") (pintype "bidirectional"))
    )
    (net (code "31") (name "/D1") (class "Default")
      (node (ref "JP1") (pin "2") (pinfunction "2_2") (pintype "passive"))
      (node (ref "JP11") (pin "2") (pinfunction "2_2") (pintype "bidirectional"))
      (node (ref "R10") (pin "2") (pinfunction "2_2") (pintype "passive"))
    )
    (net (code "32") (name "/D1_IN") (class "Default")
      (node (ref "D10") (pin "3") (pinfunction "C_3") (pintype "passive"))
      (node (ref "R10") (pin "1") (pinfunction "1_1") (pintype "passive"))
      (node (ref "U17") (pin "3") (pinfunction "PE1(TXD)_3") (pintype "bidirectional"))
    )
    (net (code "33") (name "/D2") (class "Default")
      (node (ref "JP1") (pin "3") (pinfunction "3_3") (pintype "passive"))
      (node (ref "R11") (pin "2") (pinfunction "2_2") (pintype "passive"))
    )
    (net (code "34") (name "/D2_IN") (class "Default")
      (node (ref "D11") (pin "3") (pinfunction "C_3") (pintype "passive"))
      (node (ref "R11") (pin "1") (pinfunction "1_1") (pintype "passive"))
      (node (ref "U17") (pin "18") (pinfunction "PG3_18") (pintype "bidirectional"))
    )
    (net (code "35") (name "/D3") (class "Default")
      (node (ref "JP1") (pin "4") (pinfunction "4_4") (pintype "passive"))
      (node (ref "R12") (pin "2") (pinfunction "2_2") (pintype "passive"))
    )
    (net (code "36") (name "/D3_IN") (class "Default")
      (node (ref "D12") (pin "3") (pinfunction "C_3") (pintype "passive"))
      (node (ref "R12") (pin "1") (pinfunction "1_1") (pintype "passive"))
      (node (ref "U17") (pin "19") (pinfunction "PG4_19") (pintype "bidirectional"))
    )
    (net (code "37") (name "/D4") (class "Default")
      (node (ref "JP1") (pin "5") (pinfunction "5_5") (pintype "passive"))
      (node (ref "R13") (pin "2") (pinfunction "2_2") (pintype "passive"))
    )
    (net (code "38") (name "/D4_IN") (class "Default")
      (node (ref "D13") (pin "3") (pinfunction "C_3") (pintype "passive"))
      (node (ref "R13") (pin "1") (pinfunction "1_1") (pintype "passive"))
      (node (ref "U17") (pin "8") (pinfunction "PE6_8") (pintype "bidirectional"))
    )
    (net (code "39") (name "/D5") (class "Default")
      (node (ref "JP1") (pin "6") (pinfunction "6_6") (pintype "passive"))
      (node (ref "R14") (pin "2") (pinfunction "2_2") (pintype "passive"))
    )
    (net (code "40") (name "/D5_IN") (class "Default")
      (node (ref "D14") (pin "3") (pinfunction "C_3") (pintype "passive"))
      (node (ref "R14") (pin "1") (pinfunction "1_1") (pintype "passive"))
      (node (ref "U17") (pin "15") (pinfunction "PB5(OC1A)_15") (pintype "bidirectional"))
    )
    (net (code "41") (name "/D6") (class "Default")
      (node (ref "JP1") (pin "7") (pinfunction "7_7") (pintype "passive"))
      (node (ref "R15") (pin "2") (pinfunction "2_2") (pintype "passive"))
    )
    (net (code "42") (name "/D6_IN") (class "Default")
      (node (ref "D15") (pin "3") (pinfunction "C_3") (pintype "passive"))
      (node (ref "R15") (pin "1") (pinfunction "1_1") (pintype "passive"))
      (node (ref "U17") (pin "16") (pinfunction "PB6(OC1B)_16") (pintype "bidirectional"))
    )
    (net (code "43") (name "/D7") (class "Default")
      (node (ref "JP1") (pin "8") (pinfunction "8_8") (pintype "passive"))
      (node (ref "R16") (pin "2") (pinfunction "2_2") (pintype "passive"))
    )
    (net (code "44") (name "/D7_IN") (class "Default")
      (node (ref "D22") (pin "3") (pinfunction "C_3") (pintype "passive"))
      (node (ref "R16") (pin "1") (pinfunction "1_1") (pintype "passive"))
      (node (ref "U17") (pin "40") (pinfunction "PC5_40") (pintype "bidirectional"))
    )
    (net (code "45") (name "/D8") (class "Default")
      (node (ref "JP2") (pin "1") (pinfunction "1_1") (pintype "passive"))
      (node (ref "R1") (pin "2") (pinfunction "2_2") (pintype "passive"))
    )
    (net (code "46") (name "/D8_IN") (class "Default")
      (node (ref "D1") (pin "3") (pinfunction "C_3") (pintype "passive"))
      (node (ref "R1") (pin "1") (pinfunction "1_1") (pintype "passive"))
      (node (ref "U17") (pin "41") (pinfunction "PC6_41") (pintype "bidirectional"))
    )
    (net (code "47") (name "/D9") (class "Default")
      (node (ref "JP2") (pin "2") (pinfunction "2_2") (pintype "passive"))
      (node (ref "R2") (pin "2") (pinfunction "2_2") (pintype "passive"))
    )
    (net (code "48") (name "/D9_IN") (class "Default")
      (node (ref "D2") (pin "3") (pinfunction "C_3") (pintype "passive"))
      (node (ref "R2") (pin "1") (pinfunction "1_1") (pintype "passive"))
      (node (ref "U17") (pin "42") (pinfunction "PC7_42") (pintype "bidirectional"))
    )
    (net (code "49") (name "/D10") (class "Default")
      (node (ref "JP2") (pin "3") (pinfunction "3_3") (pintype "passive"))
      (node (ref "R3") (pin "2") (pinfunction "2_2") (pintype "passive"))
    )
    (net (code "50") (name "/D11") (class "Default")
      (node (ref "JP2") (pin "4") (pinfunction "4_4") (pintype "passive"))
      (node (ref "JP8") (pin "4") (pinfunction "4_4") (pintype "bidirectional"))
      (node (ref "R4") (pin "2") (pinfunction "2_2") (pintype "passive"))
    )
    (net (code "51") (name "/D12") (class "Default")
      (node (ref "JP2") (pin "5") (pinfunction "5_5") (pintype "passive"))
      (node (ref "JP8") (pin "1") (pinfunction "1_1") (pintype "bidirectional"))
      (node (ref "R5") (pin "2") (pinfunction "2_2") (pintype "passive"))
    )
    (net (code "52") (name "/D13") (class "Default")
      (node (ref "JP2") (pin "6") (pinfunction "6_6") (pintype "passive"))
      (node (ref "JP8") (pin "3") (pinfunction "3_3") (pintype "bidirectional"))
      (node (ref "R6") (pin "2") (pinfunction "2_2") (pintype "passive"))
    )
    (net (code "53") (name "/DTR") (class "Default")
      (node (ref "C4") (pin "1") (pinfunction "1_1") (pintype "passive"))
      (node (ref "R63") (pin "1") (pinfunction "1_1") (pintype "passive"))
    )
    (net (code "54") (name "/E") (class "Default")
      (node (ref "U$1") (pin "6") (pinfunction "P$6_6") (pintype "bidirectional"))
      (node (ref "U17") (pin "39") (pinfunction "PC4_39") (pintype "bidirectional"))
    )
    (net (code "55") (name "/GND") (class "Default")
      (node (ref "C1") (pin "1") (pinfunction "1_1") (pintype "passive"))
      (node (ref "C10") (pin "2") (pinfunction "2_2") (pintype "passive"))
      (node (ref "C11") (pin "2") (pinfunction "2_2") (pintype "passive"))
      (node (ref "C12") (pin "2") (pinfunction "2_2") (pintype "passive"))
      (node (ref "C13") (pin "2") (pinfunction "2_2") (pintype "passive"))
      (node (ref "C14") (pin "2") (pinfunction "2_2") (pintype "passive"))
      (node (ref "C2") (pin "1") (pinfunction "1_1") (pintype "passive"))
      (node (ref "C3") (pin "-") (pinfunction "-_-") (pintype "passive"))
      (node (ref "C5") (pin "2") (pinfunction "2_2") (pintype "passive"))
      (node (ref "C6") (pin "2") (pinfunction "2_2") (pintype "passive"))
      (node (ref "C7") (pin "2") (pinfunction "2_2") (pintype "passive"))
      (node (ref "C8") (pin "2") (pinfunction "2_2") (pintype "passive"))
      (node (ref "C9") (pin "2") (pinfunction "2_2") (pintype "passive"))
      (node (ref "D1") (pin "1") (pinfunction "A_1") (pintype "passive"))
      (node (ref "D10") (pin "1") (pinfunction "A_1") (pintype "passive"))
      (node (ref "D11") (pin "1") (pinfunction "A_1") (pintype "passive"))
      (node (ref "D12") (pin "1") (pinfunction "A_1") (pintype "passive"))
      (node (ref "D13") (pin "1") (pinfunction "A_1") (pintype "passive"))
      (node (ref "D14") (pin "1") (pinfunction "A_1") (pintype "passive"))
      (node (ref "D15") (pin "1") (pinfunction "A_1") (pintype "passive"))
      (node (ref "D16") (pin "1") (pinfunction "A_1") (pintype "passive"))
      (node (ref "D17") (pin "1") (pinfunction "A_1") (pintype "passive"))
      (node (ref "D18") (pin "1") (pinfunction "A_1") (pintype "passive"))
      (node (ref "D19") (pin "1") (pinfunction "A_1") (pintype "passive"))
      (node (ref "D2") (pin "1") (pinfunction "A_1") (pintype "passive"))
      (node (ref "D20") (pin "1") (pinfunction "A_1") (pintype "passive"))
      (node (ref "D21") (pin "1") (pinfunction "A_1") (pintype "passive"))
      (node (ref "D22") (pin "1") (pinfunction "A_1") (pintype "passive"))
      (node (ref "D26") (pin "1") (pinfunction "A_1") (pintype "passive"))
      (node (ref "D27") (pin "1") (pinfunction "A_1") (pintype "passive"))
      (node (ref "D28") (pin "1") (pinfunction "A_1") (pintype "passive"))
      (node (ref "D29") (pin "1") (pinfunction "A_1") (pintype "passive"))
      (node (ref "D3") (pin "1") (pinfunction "A_1") (pintype "passive"))
      (node (ref "D32") (pin "1") (pinfunction "A_1") (pintype "passive"))
      (node (ref "D4") (pin "1") (pinfunction "A_1") (pintype "passive"))
      (node (ref "D5") (pin "1") (pinfunction "A_1") (pintype "passive"))
      (node (ref "D6") (pin "1") (pinfunction "A_1") (pintype "passive"))
      (node (ref "D7") (pin "1") (pinfunction "A_1") (pintype "passive"))
      (node (ref "D8") (pin "1") (pinfunction "A_1") (pintype "passive"))
      (node (ref "D9") (pin "1") (pinfunction "A_1") (pintype "passive"))
      (node (ref "IR") (pin "3") (pinfunction "3_3") (pintype "passive"))
      (node (ref "J1") (pin "GND") (pinfunction "GND_GND") (pintype "bidirectional"))
      (node (ref "J1") (pin "GNDBREAK") (pinfunction "GNDBREAK_GNDBREAK") (pintype "bidirectional"))
      (node (ref "JP10") (pin "5") (pinfunction "5_5") (pintype "bidirectional"))
      (node (ref "JP10") (pin "6") (pinfunction "6_6") (pintype "bidirectional"))
      (node (ref "JP11") (pin "5") (pinfunction "5_5") (pintype "bidirectional"))
      (node (ref "JP11") (pin "6") (pinfunction "6_6") (pintype "bidirectional"))
      (node (ref "JP2") (pin "7") (pinfunction "7_7") (pintype "passive"))
      (node (ref "JP4") (pin "6") (pinfunction "6_6") (pintype "passive"))
      (node (ref "JP4") (pin "7") (pinfunction "7_7") (pintype "passive"))
      (node (ref "JP7") (pin "1") (pinfunction "1_1") (pintype "passive"))
      (node (ref "JP7") (pin "2") (pinfunction "2_2") (pintype "passive"))
      (node (ref "JP7") (pin "3") (pinfunction "3_3") (pintype "passive"))
      (node (ref "JP7") (pin "4") (pinfunction "4_4") (pintype "passive"))
      (node (ref "JP8") (pin "6") (pinfunction "6_6") (pintype "bidirectional"))
      (node (ref "JP9") (pin "GND") (pinfunction "GND_GND") (pintype "bidirectional"))
      (node (ref "POWER") (pin "P$2") (pinfunction "P$2_P$2") (pintype "bidirectional"))
      (node (ref "R26") (pin "1") (pinfunction "1_1") (pintype "passive"))
      (node (ref "R31") (pin "1") (pinfunction "1_1") (pintype "passive"))
      (node (ref "R32") (pin "1") (pinfunction "1_1") (pintype "passive"))
      (node (ref "R36") (pin "1") (pinfunction "1_1") (pintype "passive"))
      (node (ref "R41") (pin "1") (pinfunction "1_1") (pintype "passive"))
      (node (ref "R46") (pin "1") (pinfunction "1_1") (pintype "passive"))
      (node (ref "R51") (pin "1") (pinfunction "1_1") (pintype "passive"))
      (node (ref "R52") (pin "1") (pinfunction "1_1") (pintype "passive"))
      (node (ref "R53") (pin "1") (pinfunction "1_1") (pintype "passive"))
      (node (ref "R62") (pin "1") (pinfunction "1_1") (pintype "passive"))
      (node (ref "R65") (pin "2") (pinfunction "2_2") (pintype "passive"))
      (node (ref "R66") (pin "1") (pinfunction "1_1") (pintype "passive"))
      (node (ref "RESET") (pin "1") (pinfunction "1_1") (pintype "passive"))
      (node (ref "RESET") (pin "2") (pinfunction "2_2") (pintype "passive"))
      (node (ref "S2") (pin "1") (pinfunction "1_1") (pintype "passive"))
      (node (ref "S2") (pin "2") (pinfunction "2_2") (pintype "passive"))
      (node (ref "U$1") (pin "1") (pinfunction "P$1_1") (pintype "bidirectional"))
      (node (ref "U$1") (pin "5") (pinfunction "P$5_5") (pintype "bidirectional"))
      (node (ref "U$11") (pin "2") (pinfunction "S_2") (pintype "bidirectional"))
      (node (ref "U$2") (pin "3") (pinfunction "E_3") (pintype "passive"))
      (node (ref "U$3") (pin "GND@N1") (pinfunction "PGND_GND@N1") (pintype "bidirectional"))
      (node (ref "U$3") (pin "GND@N2") (pinfunction "PGND_GND@N2") (pintype "bidirectional"))
      (node (ref "U$3") (pin "GND@N3") (pinfunction "PGND_GND@N3") (pintype "bidirectional"))
      (node (ref "U$3") (pin "GND@N4") (pinfunction "PGND_GND@N4") (pintype "bidirectional"))
      (node (ref "U$3") (pin "GND@N5") (pinfunction "PGND_GND@N5") (pintype "bidirectional"))
      (node (ref "U$3") (pin "GND@N6") (pinfunction "PGND_GND@N6") (pintype "bidirectional"))
      (node (ref "U$3") (pin "GND@N7") (pinfunction "PGND_GND@N7") (pintype "bidirectional"))
      (node (ref "U$3") (pin "GND@N8") (pinfunction "PGND_GND@N8") (pintype "bidirectional"))
      (node (ref "U$3") (pin "P$11") (pinfunction "PGND_P$11") (pintype "bidirectional"))
      (node (ref "U$3") (pin "P$7") (pinfunction "GND_P$7") (pintype "bidirectional"))
      (node (ref "U$5") (pin "3") (pinfunction "ANODE_3") (pintype "bidirectional"))
      (node (ref "U$8") (pin "P$10") (pinfunction "GND2_P$10") (pintype "bidirectional"))
      (node (ref "U$8") (pin "P$12") (pinfunction "GND3_P$12") (pintype "bidirectional"))
      (node (ref "U$8") (pin "P$13") (pinfunction "NC3_P$13") (pintype "bidirectional"))
      (node (ref "U$8") (pin "P$5") (pinfunction "GND1_P$5") (pintype "bidirectional"))
      (node (ref "U$8") (pin "P$7") (pinfunction "SA0_P$7") (pintype "bidirectional"))
      (node (ref "U$8") (pin "P$8") (pinfunction "NC2_P$8") (pintype "bidirectional"))
      (node (ref "U1") (pin "18") (pinfunction "GND2_18") (pintype "power_in"))
      (node (ref "U1") (pin "21") (pinfunction "GND3_21") (pintype "power_in"))
      (node (ref "U1") (pin "25") (pinfunction "AGND_25") (pintype "power_in"))
      (node (ref "U1") (pin "26") (pinfunction "TEST_26") (pintype "input"))
      (node (ref "U1") (pin "7") (pinfunction "GND1_7") (pintype "power_in"))
      (node (ref "U10") (pin "GND") (pinfunction "GND_PPAD_GND") (pintype "bidirectional"))
      (node (ref "U10") (pin "P$5") (pinfunction "GND1_P$5") (pintype "bidirectional"))
      (node (ref "U10") (pin "P$6") (pinfunction "GND2_P$6") (pintype "bidirectional"))
      (node (ref "U12") (pin "4") (pinfunction "V-_4") (pintype "power_in"))
      (node (ref "U16") (pin "4") (pinfunction "V-_4") (pintype "power_in"))
      (node (ref "U16") (pin "5") (pinfunction "+IN_5") (pintype "input"))
      (node (ref "U16") (pin "6") (pinfunction "-IN_6") (pintype "input"))
      (node (ref "U17") (pin "22") (pinfunction "GND1_22") (pintype "bidirectional"))
      (node (ref "U17") (pin "53") (pinfunction "GND2_53") (pintype "bidirectional"))
      (node (ref "U17") (pin "63") (pinfunction "GND3_63") (pintype "bidirectional"))
      (node (ref "U4") (pin "13") (pinfunction "GND_13") (pintype "bidirectional"))
      (node (ref "U4") (pin "21") (pinfunction "GND1_21") (pintype "bidirectional"))
      (node (ref "U4") (pin "22") (pinfunction "GND2_22") (pintype "bidirectional"))
      (node (ref "U4") (pin "34") (pinfunction "PIO11_34") (pintype "bidirectional"))
      (node (ref "U7") (pin "P$2") (pinfunction "GND_P$2") (pintype "bidirectional"))
      (node (ref "U8") (pin "P$2") (pinfunction "GND_P$2") (pintype "bidirectional"))
      (node (ref "U9") (pin "GND") (pinfunction "GND_PPAD_GND") (pintype "bidirectional"))
      (node (ref "U9") (pin "P$5") (pinfunction "GND1_P$5") (pintype "bidirectional"))
      (node (ref "U9") (pin "P$6") (pinfunction "GND2_P$6") (pintype "bidirectional"))
    )
    (net (code "56") (name "/IR") (class "Default")
      (node (ref "IR") (pin "1") (pinfunction "1_1") (pintype "passive"))
      (node (ref "U17") (pin "25") (pinfunction "PD0_25") (pintype "bidirectional"))
    )
    (net (code "57") (name "/LCD0") (class "Default")
      (node (ref "R34") (pin "2") (pinfunction "2_2") (pintype "passive"))
      (node (ref "U17") (pin "51") (pinfunction "PA0_51") (pintype "bidirectional"))
    )
    (net (code "58") (name "/LCD1") (class "Default")
      (node (ref "U$1") (pin "8") (pinfunction "P$8_8") (pintype "bidirectional"))
      (node (ref "U17") (pin "50") (pinfunction "PA1_50") (pintype "bidirectional"))
    )
    (net (code "59") (name "/LCD2") (class "Default")
      (node (ref "U$1") (pin "9") (pinfunction "P$9_9") (pintype "bidirectional"))
      (node (ref "U17") (pin "49") (pinfunction "PA2_49") (pintype "bidirectional"))
    )
    (net (code "60") (name "/LCD3") (class "Default")
      (node (ref "U$1") (pin "10") (pinfunction "P$10_10") (pintype "bidirectional"))
      (node (ref "U17") (pin "48") (pinfunction "PA3_48") (pintype "bidirectional"))
    )
    (net (code "61") (name "/LCD4") (class "Default")
      (node (ref "U$1") (pin "11") (pinfunction "P$11_11") (pintype "bidirectional"))
      (node (ref "U17") (pin "47") (pinfunction "PA4_47") (pintype "bidirectional"))
    )
    (net (code "62") (name "/LCD5") (class "Default")
      (node (ref "U$1") (pin "12") (pinfunction "P$12_12") (pintype "bidirectional"))
      (node (ref "U17") (pin "46") (pinfunction "PA5_46") (pintype "bidirectional"))
    )
    (net (code "63") (name "/LCD6") (class "Default")
      (node (ref "U$1") (pin "13") (pinfunction "P$13_13") (pintype "bidirectional"))
      (node (ref "U17") (pin "45") (pinfunction "PA6_45") (pintype "bidirectional"))
    )
    (net (code "64") (name "/LCD7") (class "Default")
      (node (ref "U$1") (pin "14") (pinfunction "P$14_14") (pintype "bidirectional"))
      (node (ref "U17") (pin "44") (pinfunction "PA7_44") (pintype "bidirectional"))
    )
    (net (code "65") (name "/LED0") (class "Default")
      (node (ref "D30") (pin "A") (pinfunction "A_A") (pintype "passive"))
      (node (ref "U17") (pin "34") (pinfunction "PG1_34") (pintype "bidirectional"))
    )
    (net (code "66") (name "/LED1") (class "Default")
      (node (ref "D31") (pin "A") (pinfunction "A_A") (pintype "passive"))
      (node (ref "U17") (pin "33") (pinfunction "PG0_33") (pintype "bidirectional"))
    )
    (net (code "67") (name "/M0_DIR0") (class "Default")
      (node (ref "U17") (pin "29") (pinfunction "PD4_29") (pintype "bidirectional"))
      (node (ref "U9") (pin "P$9") (pinfunction "IN1_P$9") (pintype "bidirectional"))
    )
    (net (code "68") (name "/M0_DIR1") (class "Default")
      (node (ref "U17") (pin "30") (pinfunction "PD5_30") (pintype "bidirectional"))
      (node (ref "U9") (pin "P$11") (pinfunction "IN2_P$11") (pintype "bidirectional"))
    )
    (net (code "69") (name "/M0_EN") (class "Default")
      (node (ref "U17") (pin "14") (pinfunction "PB4(OC0A)_14") (pintype "bidirectional"))
      (node (ref "U9") (pin "P$10") (pinfunction "EN1_P$10") (pintype "bidirectional"))
      (node (ref "U9") (pin "P$12") (pinfunction "EN2_P$12") (pintype "bidirectional"))
    )
    (net (code "70") (name "/M1_DIR0") (class "Default")
      (node (ref "U10") (pin "P$9") (pinfunction "IN1_P$9") (pintype "bidirectional"))
      (node (ref "U17") (pin "31") (pinfunction "PD6_31") (pintype "bidirectional"))
    )
    (net (code "71") (name "/M1_DIR1") (class "Default")
      (node (ref "U10") (pin "P$11") (pinfunction "IN2_P$11") (pintype "bidirectional"))
      (node (ref "U17") (pin "32") (pinfunction "PD7_32") (pintype "bidirectional"))
    )
    (net (code "72") (name "/M1_EN") (class "Default")
      (node (ref "U10") (pin "P$10") (pinfunction "EN1_P$10") (pintype "bidirectional"))
      (node (ref "U10") (pin "P$12") (pinfunction "EN2_P$12") (pintype "bidirectional"))
      (node (ref "U17") (pin "17") (pinfunction "PB7(OC2A)_17") (pintype "bidirectional"))
    )
    (net (code "73") (name "/MISO") (class "Default")
      (node (ref "D5") (pin "3") (pinfunction "C_3") (pintype "passive"))
      (node (ref "R5") (pin "1") (pinfunction "1_1") (pintype "passive"))
      (node (ref "U17") (pin "13") (pinfunction "PB3(MISO)_13") (pintype "bidirectional"))
    )
    (net (code "74") (name "/MOSI") (class "Default")
      (node (ref "D4") (pin "3") (pinfunction "C_3") (pintype "passive"))
      (node (ref "R4") (pin "1") (pinfunction "1_1") (pintype "passive"))
      (node (ref "U17") (pin "12") (pinfunction "PB2(MOSI)_12") (pintype "bidirectional"))
    )
    (net (code "75") (name "/PWR_GATE") (class "Default")
      (node (ref "Q1") (pin "3") (pinfunction "D_3") (pintype "bidirectional"))
      (node (ref "R32") (pin "2") (pinfunction "2_2") (pintype "passive"))
      (node (ref "U$6") (pin "G1") (pinfunction "G1_G1") (pintype "bidirectional"))
      (node (ref "U$6") (pin "G2") (pinfunction "G2_G2") (pintype "bidirectional"))
    )
    (net (code "76") (name "/PWR_SW") (class "Default")
      (node (ref "Q2") (pin "2") (pinfunction "S_2") (pintype "bidirectional"))
      (node (ref "R44") (pin "1") (pinfunction "1_1") (pintype "passive"))
      (node (ref "U$6") (pin "S2") (pinfunction "S2_S2") (pintype "bidirectional"))
      (node (ref "U$7") (pin "S2") (pinfunction "S2_S2") (pintype "bidirectional"))
    )
    (net (code "77") (name "/RESET") (class "Default")
      (node (ref "C4") (pin "2") (pinfunction "2_2") (pintype "passive"))
      (node (ref "R39") (pin "1") (pinfunction "1_1") (pintype "passive"))
      (node (ref "R40") (pin "2") (pinfunction "2_2") (pintype "passive"))
      (node (ref "R56") (pin "1") (pinfunction "1_1") (pintype "passive"))
      (node (ref "RESET") (pin "3") (pinfunction "3_3") (pintype "passive"))
      (node (ref "RESET") (pin "4") (pinfunction "4_4") (pintype "passive"))
      (node (ref "U17") (pin "20") (pinfunction "RESET/PG5_20") (pintype "bidirectional"))
    )
    (net (code "78") (name "/RS") (class "Default")
      (node (ref "R33") (pin "1") (pinfunction "1_1") (pintype "passive"))
      (node (ref "U17") (pin "54") (pinfunction "PF7(ADC7)_54") (pintype "bidirectional"))
    )
    (net (code "79") (name "/RX") (class "Default")
      (node (ref "U1") (pin "1") (pinfunction "TXD_1") (pintype "output"))
      (node (ref "U17") (pin "28") (pinfunction "PD3_28") (pintype "bidirectional"))
    )
    (net (code "80") (name "/SCK") (class "Default")
      (node (ref "D6") (pin "3") (pinfunction "C_3") (pintype "passive"))
      (node (ref "R6") (pin "1") (pinfunction "1_1") (pintype "passive"))
      (node (ref "U17") (pin "11") (pinfunction "PB1(SCK)_11") (pintype "bidirectional"))
    )
    (net (code "81") (name "/SCL0") (class "Default")
      (node (ref "JP2") (pin "9") (pinfunction "9_9") (pintype "passive"))
      (node (ref "R7") (pin "2") (pinfunction "2_2") (pintype "passive"))
    )
    (net (code "82") (name "/SCL_5V") (class "Default")
      (node (ref "R60") (pin "1") (pinfunction "1_1") (pintype "passive"))
      (node (ref "U$10") (pin "3") (pinfunction "D_3") (pintype "bidirectional"))
      (node (ref "U17") (pin "6") (pinfunction "PE4(SCL)_6") (pintype "bidirectional"))
    )
    (net (code "83") (name "/SCL_IN") (class "Default")
      (node (ref "D7") (pin "3") (pinfunction "C_3") (pintype "passive"))
      (node (ref "R38") (pin "1") (pinfunction "1_1") (pintype "passive"))
      (node (ref "R7") (pin "1") (pinfunction "1_1") (pintype "passive"))
      (node (ref "U$10") (pin "2") (pinfunction "S_2") (pintype "bidirectional"))
      (node (ref "U$8") (pin "P$4") (pinfunction "SCL_P$4") (pintype "bidirectional"))
    )
    (net (code "84") (name "/SDA0") (class "Default")
      (node (ref "JP2") (pin "10") (pinfunction "10_10") (pintype "passive"))
      (node (ref "R8") (pin "2") (pinfunction "2_2") (pintype "passive"))
    )
    (net (code "85") (name "/SDA_5V") (class "Default")
      (node (ref "R58") (pin "1") (pinfunction "1_1") (pintype "passive"))
      (node (ref "U$9") (pin "3") (pinfunction "D_3") (pintype "bidirectional"))
      (node (ref "U17") (pin "7") (pinfunction "PE5(SDA)_7") (pintype "bidirectional"))
    )
    (net (code "86") (name "/SDA_IN") (class "Default")
      (node (ref "D8") (pin "3") (pinfunction "C_3") (pintype "passive"))
      (node (ref "R37") (pin "1") (pinfunction "1_1") (pintype "passive"))
      (node (ref "R8") (pin "1") (pinfunction "1_1") (pintype "passive"))
      (node (ref "U$8") (pin "P$6") (pinfunction "SDA_P$6") (pintype "bidirectional"))
      (node (ref "U$9") (pin "2") (pinfunction "S_2") (pintype "bidirectional"))
    )
    (net (code "87") (name "/SERVO0") (class "Default")
      (node (ref "JP3") (pin "1") (pinfunction "1_1") (pintype "passive"))
      (node (ref "R47") (pin "2") (pinfunction "2_2") (pintype "passive"))
    )
    (net (code "88") (name "/SERVO0_IN") (class "Default")
      (node (ref "D26") (pin "3") (pinfunction "C_3") (pintype "passive"))
      (node (ref "R47") (pin "1") (pinfunction "1_1") (pintype "passive"))
      (node (ref "U17") (pin "35") (pinfunction "PC0_35") (pintype "bidirectional"))
    )
    (net (code "89") (name "/SERVO1") (class "Default")
      (node (ref "JP3") (pin "2") (pinfunction "2_2") (pintype "passive"))
      (node (ref "R48") (pin "2") (pinfunction "2_2") (pintype "passive"))
    )
    (net (code "90") (name "/SERVO1_IN") (class "Default")
      (node (ref "D27") (pin "3") (pinfunction "C_3") (pintype "passive"))
      (node (ref "R48") (pin "1") (pinfunction "1_1") (pintype "passive"))
      (node (ref "U17") (pin "36") (pinfunction "PC1_36") (pintype "bidirectional"))
    )
    (net (code "91") (name "/SERVO2") (class "Default")
      (node (ref "JP3") (pin "3") (pinfunction "3_3") (pintype "passive"))
      (node (ref "R49") (pin "2") (pinfunction "2_2") (pintype "passive"))
    )
    (net (code "92") (name "/SERVO2_IN") (class "Default")
      (node (ref "D28") (pin "3") (pinfunction "C_3") (pintype "passive"))
      (node (ref "R49") (pin "1") (pinfunction "1_1") (pintype "passive"))
      (node (ref "U17") (pin "37") (pinfunction "PC2_37") (pintype "bidirectional"))
    )
    (net (code "93") (name "/SERVO3") (class "Default")
      (node (ref "JP3") (pin "4") (pinfunction "4_4") (pintype "passive"))
      (node (ref "R50") (pin "2") (pinfunction "2_2") (pintype "passive"))
    )
    (net (code "94") (name "/SERVO3_IN") (class "Default")
      (node (ref "D29") (pin "3") (pinfunction "C_3") (pintype "passive"))
      (node (ref "R50") (pin "1") (pinfunction "1_1") (pintype "passive"))
      (node (ref "U17") (pin "38") (pinfunction "PC3_38") (pintype "bidirectional"))
    )
    (net (code "95") (name "/SS") (class "Default")
      (node (ref "D3") (pin "3") (pinfunction "C_3") (pintype "passive"))
      (node (ref "R3") (pin "1") (pinfunction "1_1") (pintype "passive"))
      (node (ref "U17") (pin "10") (pinfunction "PB0(SS)_10") (pintype "bidirectional"))
    )
    (net (code "96") (name "/SW1") (class "Default")
      (node (ref "S2") (pin "3") (pinfunction "3_3") (pintype "passive"))
      (node (ref "S2") (pin "4") (pinfunction "4_4") (pintype "passive"))
      (node (ref "U17") (pin "9") (pinfunction "PE7_9") (pintype "bidirectional"))
    )
    (net (code "97") (name "/TX") (class "Default")
      (node (ref "U1") (pin "5") (pinfunction "RXD_5") (pintype "input"))
      (node (ref "U17") (pin "27") (pinfunction "PD2_27") (pintype "bidirectional"))
    )
    (net (code "98") (name "/USBGATE") (class "Default")
      (node (ref "Q1") (pin "1") (pinfunction "G_1") (pintype "bidirectional"))
      (node (ref "R42") (pin "1") (pinfunction "1_1") (pintype "passive"))
      (node (ref "U$7") (pin "G1") (pinfunction "G1_G1") (pintype "bidirectional"))
      (node (ref "U$7") (pin "G2") (pinfunction "G2_G2") (pintype "bidirectional"))
      (node (ref "U16") (pin "1") (pinfunction "OUT_1") (pintype "output"))
    )
    (net (code "99") (name "/USB_2.5V") (class "Default")
      (node (ref "R64") (pin "1") (pinfunction "1_1") (pintype "passive"))
      (node (ref "R66") (pin "2") (pinfunction "2_2") (pintype "passive"))
      (node (ref "U16") (pin "2") (pinfunction "-IN_2") (pintype "input"))
    )
    (net (code "100") (name "/USB_5V") (class "Default")
      (node (ref "D24") (pin "2") (pinfunction "A2_2") (pintype "passive"))
      (node (ref "F2") (pin "2") (pinfunction "2_2") (pintype "passive"))
      (node (ref "R64") (pin "2") (pinfunction "2_2") (pintype "passive"))
      (node (ref "U$7") (pin "S1") (pinfunction "S1_S1") (pintype "bidirectional"))
      (node (ref "U16") (pin "8") (pinfunction "V+_8") (pintype "power_in"))
    )
    (net (code "101") (name "/VIN") (class "Default")
      (node (ref "J1") (pin "PWR") (pinfunction "PWR_PWR") (pintype "bidirectional"))
      (node (ref "R35") (pin "2") (pinfunction "2_2") (pintype "passive"))
      (node (ref "U$12") (pin "1") (pinfunction "1_1") (pintype "passive"))
    )
    (net (code "102") (name "/VIN1") (class "Default")
      (node (ref "D24") (pin "1") (pinfunction "A1_1") (pintype "passive"))
      (node (ref "U$12") (pin "2") (pinfunction "2_2") (pintype "passive"))
      (node (ref "U$6") (pin "S1") (pinfunction "S1_S1") (pintype "bidirectional"))
    )
    (net (code "103") (name "/VIN_F") (class "Default")
      (node (ref "C13") (pin "1") (pinfunction "1_1") (pintype "passive"))
      (node (ref "JP4") (pin "8") (pinfunction "8_8") (pintype "passive"))
      (node (ref "JP6") (pin "1") (pinfunction "1_1") (pintype "passive"))
      (node (ref "JP6") (pin "2") (pinfunction "2_2") (pintype "passive"))
      (node (ref "JP6") (pin "3") (pinfunction "3_3") (pintype "passive"))
      (node (ref "JP6") (pin "4") (pinfunction "4_4") (pintype "passive"))
      (node (ref "Q2") (pin "3") (pinfunction "D_3") (pintype "bidirectional"))
      (node (ref "R45") (pin "2") (pinfunction "2_2") (pintype "passive"))
      (node (ref "U$3") (pin "P$2") (pinfunction "VIN_P$2") (pintype "bidirectional"))
      (node (ref "U$3") (pin "P$3") (pinfunction "EN_P$3") (pintype "bidirectional"))
      (node (ref "U$3") (pin "P$4") (pinfunction "PS/SYNC_P$4") (pintype "bidirectional"))
      (node (ref "U10") (pin "P$1") (pinfunction "VM1_P$1") (pintype "bidirectional"))
      (node (ref "U10") (pin "P$2") (pinfunction "VM2_P$2") (pintype "bidirectional"))
      (node (ref "U9") (pin "P$1") (pinfunction "VM1_P$1") (pintype "bidirectional"))
      (node (ref "U9") (pin "P$2") (pinfunction "VM2_P$2") (pintype "bidirectional"))
    )
    (net (code "104") (name "/VREG_OUT") (class "Default")
      (node (ref "C11") (pin "1") (pinfunction "1_1") (pintype "passive"))
      (node (ref "C12") (pin "1") (pinfunction "1_1") (pintype "passive"))
      (node (ref "F3") (pin "1") (pinfunction "1_1") (pintype "passive"))
      (node (ref "U$3") (pin "P$8") (pinfunction "FB_P$8") (pintype "bidirectional"))
      (node (ref "U$3") (pin "P$9") (pinfunction "VOUT_P$9") (pintype "bidirectional"))
    )
    (net (code "105") (name "Net-(D23-PadA)") (class "Default")
      (node (ref "D23") (pin "A") (pinfunction "A_A") (pintype "passive"))
      (node (ref "R29") (pin "2") (pinfunction "2_2") (pintype "passive"))
    )
    (net (code "106") (name "Net-(D24-CC)") (class "Default")
      (node (ref "D24") (pin "3") (pinfunction "CC_3") (pintype "passive"))
      (node (ref "Q1") (pin "2") (pinfunction "S_2") (pintype "bidirectional"))
      (node (ref "R42") (pin "2") (pinfunction "2_2") (pintype "passive"))
    )
    (net (code "107") (name "Net-(D25-PadC)") (class "Default")
      (node (ref "D25") (pin "C") (pinfunction "C_C") (pintype "passive"))
      (node (ref "R41") (pin "2") (pinfunction "2_2") (pintype "passive"))
    )
    (net (code "108") (name "Net-(D30-PadC)") (class "Default")
      (node (ref "D30") (pin "C") (pinfunction "C_C") (pintype "passive"))
      (node (ref "R51") (pin "2") (pinfunction "2_2") (pintype "passive"))
    )
    (net (code "109") (name "Net-(D31-PadC)") (class "Default")
      (node (ref "D31") (pin "C") (pinfunction "C_C") (pintype "passive"))
      (node (ref "R52") (pin "2") (pinfunction "2_2") (pintype "passive"))
    )
    (net (code "110") (name "Net-(D34-PadA)") (class "Default")
      (node (ref "D34") (pin "A") (pinfunction "A_A") (pintype "passive"))
      (node (ref "R57") (pin "2") (pinfunction "2_2") (pintype "passive"))
    )
    (net (code "111") (name "Net-(F2-Pad1)") (class "Default")
      (node (ref "F2") (pin "1") (pinfunction "1_1") (pintype "passive"))
      (node (ref "JP9") (pin "VBUS") (pinfunction "VBUS_VBUS") (pintype "bidirectional"))
    )
    (net (code "112") (name "Net-(JP4-Pad3)") (class "Default")
      (node (ref "JP4") (pin "3") (pinfunction "3_3") (pintype "passive"))
      (node (ref "R56") (pin "2") (pinfunction "2_2") (pintype "passive"))
    )
    (net (code "113") (name "Net-(JP8-Pad5)") (class "Default")
      (node (ref "JP8") (pin "5") (pinfunction "5_5") (pintype "bidirectional"))
      (node (ref "R39") (pin "2") (pinfunction "2_2") (pintype "passive"))
    )
    (net (code "114") (name "Net-(POWER-PadP$1)") (class "Default")
      (node (ref "POWER") (pin "P$1") (pinfunction "P$1_P$1") (pintype "bidirectional"))
      (node (ref "R43") (pin "2") (pinfunction "2_2") (pintype "passive"))
    )
    (net (code "115") (name "Net-(Q2-G)") (class "Default")
      (node (ref "Q2") (pin "1") (pinfunction "G_1") (pintype "bidirectional"))
      (node (ref "R43") (pin "1") (pinfunction "1_1") (pintype "passive"))
      (node (ref "R44") (pin "2") (pinfunction "2_2") (pintype "passive"))
    )
    (net (code "116") (name "Net-(Q3-G)") (class "Default")
      (node (ref "Q3") (pin "1") (pinfunction "G_1") (pintype "bidirectional"))
      (node (ref "R25") (pin "1") (pinfunction "1_1") (pintype "passive"))
      (node (ref "U12") (pin "7") (pinfunction "OUT_7") (pintype "output"))
    )
    (net (code "117") (name "Net-(Q4-G)") (class "Default")
      (node (ref "Q4") (pin "1") (pinfunction "G_1") (pintype "bidirectional"))
      (node (ref "R30") (pin "1") (pinfunction "1_1") (pintype "passive"))
      (node (ref "U12") (pin "1") (pinfunction "OUT_1") (pintype "output"))
    )
    (net (code "118") (name "Net-(U$1-P$3)") (class "Default")
      (node (ref "U$1") (pin "3") (pinfunction "P$3_3") (pintype "bidirectional"))
      (node (ref "U$2") (pin "2") (pinfunction "S_2") (pintype "passive"))
    )
    (net (code "119") (name "Net-(U$1-P$4)") (class "Default")
      (node (ref "R33") (pin "2") (pinfunction "2_2") (pintype "passive"))
      (node (ref "U$1") (pin "4") (pinfunction "P$4_4") (pintype "bidirectional"))
    )
    (net (code "120") (name "Net-(U$1-P$7)") (class "Default")
      (node (ref "R34") (pin "1") (pinfunction "1_1") (pintype "passive"))
      (node (ref "U$1") (pin "7") (pinfunction "P$7_7") (pintype "bidirectional"))
    )
    (net (code "121") (name "Net-(U$3-L1)") (class "Default")
      (node (ref "U$3") (pin "P$1") (pinfunction "L1_P$1") (pintype "bidirectional"))
      (node (ref "U$4") (pin "P$1") (pinfunction "1_P$1") (pintype "passive"))
    )
    (net (code "122") (name "Net-(U$3-L2)") (class "Default")
      (node (ref "U$3") (pin "P$10") (pinfunction "L2_P$10") (pintype "bidirectional"))
      (node (ref "U$4") (pin "P$2") (pinfunction "2_P$2") (pintype "passive"))
    )
    (net (code "123") (name "Net-(U$3-PG)") (class "Default")
      (node (ref "R28") (pin "2") (pinfunction "2_2") (pintype "passive"))
      (node (ref "U$3") (pin "P$5") (pinfunction "PG_P$5") (pintype "bidirectional"))
    )
    (net (code "124") (name "Net-(U$3-VAUX)") (class "Default")
      (node (ref "C10") (pin "1") (pinfunction "1_1") (pintype "passive"))
      (node (ref "U$3") (pin "P$6") (pinfunction "VAUX_P$6") (pintype "bidirectional"))
    )
    (net (code "125") (name "Net-(U$6-D1-PadD1@1)") (class "Default")
      (node (ref "U$6") (pin "D1@1") (pinfunction "D1_D1@1") (pintype "bidirectional"))
      (node (ref "U$6") (pin "D1@2") (pinfunction "D1_D1@2") (pintype "bidirectional"))
      (node (ref "U$6") (pin "D2@1") (pinfunction "D2_D2@1") (pintype "bidirectional"))
      (node (ref "U$6") (pin "D2@2") (pinfunction "D2_D2@2") (pintype "bidirectional"))
    )
    (net (code "126") (name "Net-(U$7-D1-PadD1@1)") (class "Default")
      (node (ref "U$7") (pin "D1@1") (pinfunction "D1_D1@1") (pintype "bidirectional"))
      (node (ref "U$7") (pin "D1@2") (pinfunction "D1_D1@2") (pintype "bidirectional"))
      (node (ref "U$7") (pin "D2@1") (pinfunction "D2_D2@1") (pintype "bidirectional"))
      (node (ref "U$7") (pin "D2@2") (pinfunction "D2_D2@2") (pintype "bidirectional"))
    )
    (net (code "127") (name "Net-(U$8-BYP)") (class "Default")
      (node (ref "C5") (pin "1") (pinfunction "1_1") (pintype "passive"))
      (node (ref "U$8") (pin "P$2") (pinfunction "BYP_P$2") (pintype "bidirectional"))
    )
    (net (code "128") (name "Net-(U1-DTR)") (class "Default")
      (node (ref "R63") (pin "2") (pinfunction "2_2") (pintype "passive"))
      (node (ref "U1") (pin "2") (pinfunction "DTR_2") (pintype "bidirectional"))
    )
    (net (code "129") (name "Net-(U1-RXLED)") (class "Default")
      (node (ref "D34") (pin "C") (pinfunction "C_C") (pintype "passive"))
      (node (ref "U1") (pin "22") (pinfunction "RXLED_22") (pintype "bidirectional"))
    )
    (net (code "130") (name "Net-(U1-TXLED)") (class "Default")
      (node (ref "D23") (pin "C") (pinfunction "C_C") (pintype "passive"))
      (node (ref "U1") (pin "23") (pinfunction "TXLED_23") (pintype "bidirectional"))
    )
    (net (code "131") (name "Net-(U1-USBDM)") (class "Default")
      (node (ref "JP9") (pin "D-") (pinfunction "D-_D-") (pintype "bidirectional"))
      (node (ref "U1") (pin "16") (pinfunction "USBDM_16") (pintype "bidirectional"))
    )
    (net (code "132") (name "Net-(U1-USBDP)") (class "Default")
      (node (ref "JP9") (pin "D+") (pinfunction "D+_D+") (pintype "bidirectional"))
      (node (ref "U1") (pin "15") (pinfunction "USBDP_15") (pintype "bidirectional"))
    )
    (net (code "133") (name "Net-(U4-RX)") (class "Default")
      (node (ref "R61") (pin "1") (pinfunction "1_1") (pintype "passive"))
      (node (ref "R62") (pin "2") (pinfunction "2_2") (pintype "passive"))
      (node (ref "U4") (pin "2") (pinfunction "RX_2") (pintype "bidirectional"))
    )
    (net (code "134") (name "Net-(U8-EN)") (class "Default")
      (node (ref "R65") (pin "1") (pinfunction "1_1") (pintype "passive"))
      (node (ref "U8") (pin "P$3") (pinfunction "EN_P$3") (pintype "bidirectional"))
    )
    (net (code "135") (name "Net-(U8-ILIM)") (class "Default")
      (node (ref "R53") (pin "2") (pinfunction "2_2") (pintype "passive"))
      (node (ref "U8") (pin "P$5") (pinfunction "ILIM_P$5") (pintype "bidirectional"))
    )
    (net (code "136") (name "Net-(U12A-+IN)") (class "Default")
      (node (ref "R27") (pin "1") (pinfunction "1_1") (pintype "passive"))
      (node (ref "R31") (pin "2") (pinfunction "2_2") (pintype "passive"))
      (node (ref "U12") (pin "3") (pinfunction "+IN_3") (pintype "input"))
    )
    (net (code "137") (name "Net-(U12B-+IN)") (class "Default")
      (node (ref "R24") (pin "1") (pinfunction "1_1") (pintype "passive"))
      (node (ref "R26") (pin "2") (pinfunction "2_2") (pintype "passive"))
      (node (ref "U12") (pin "5") (pinfunction "+IN_5") (pintype "input"))
    )
    (net (code "138") (name "Net-(U16A-+IN)") (class "Default")
      (node (ref "R35") (pin "1") (pinfunction "1_1") (pintype "passive"))
      (node (ref "R36") (pin "2") (pinfunction "2_2") (pintype "passive"))
      (node (ref "U16") (pin "3") (pinfunction "+IN_3") (pintype "input"))
    )
    (net (code "139") (name "Net-(U17-PF6(ADC6))") (class "Default")
      (node (ref "R45") (pin "1") (pinfunction "1_1") (pintype "passive"))
      (node (ref "R46") (pin "2") (pinfunction "2_2") (pintype "passive"))
      (node (ref "U17") (pin "55") (pinfunction "PF6(ADC6)_55") (pintype "bidirectional"))
    )
    (net (code "140") (name "Net-(U17-PG2)") (class "Default")
      (node (ref "R55") (pin "2") (pinfunction "2_2") (pintype "passive"))
      (node (ref "U17") (pin "43") (pinfunction "PG2_43") (pintype "bidirectional"))
    )
    (net (code "141") (name "Net-(U17-XTAL1)") (class "Default")
      (node (ref "C1") (pin "2") (pinfunction "2_2") (pintype "passive"))
      (node (ref "U17") (pin "24") (pinfunction "XTAL1_24") (pintype "bidirectional"))
      (node (ref "Y1") (pin "P$1") (pinfunction "1_P$1") (pintype "passive"))
    )
    (net (code "142") (name "Net-(U17-XTAL2)") (class "Default")
      (node (ref "C2") (pin "2") (pinfunction "2_2") (pintype "passive"))
      (node (ref "U17") (pin "23") (pinfunction "XTAL2_23") (pintype "bidirectional"))
      (node (ref "Y1") (pin "P$2") (pinfunction "2_P$2") (pintype "passive"))
    )
    (net (code "143") (name "unconnected-(JP4-Pad1)") (class "Default")
      (node (ref "JP4") (pin "1") (pinfunction "1_1") (pintype "passive"))
    )
    (net (code "144") (name "unconnected-(JP12-Pad1)") (class "Default")
      (node (ref "JP12") (pin "1") (pinfunction "1_1") (pintype "passive"))
    )
    (net (code "145") (name "unconnected-(JP12-Pad2)") (class "Default")
      (node (ref "JP12") (pin "2") (pinfunction "2_2") (pintype "passive"))
    )
    (net (code "146") (name "unconnected-(R55-Pad1)") (class "Default")
      (node (ref "R55") (pin "1") (pinfunction "1_1") (pintype "passive"))
    )
    (net (code "147") (name "unconnected-(U$8-INT2-PadP$9)") (class "Default")
      (node (ref "U$8") (pin "P$9") (pinfunction "INT2_P$9") (pintype "bidirectional"))
    )
    (net (code "148") (name "unconnected-(U$8-NC1-PadP$3)") (class "Default")
      (node (ref "U$8") (pin "P$3") (pinfunction "NC1_P$3") (pintype "bidirectional"))
    )
    (net (code "149") (name "unconnected-(U1-3V3OUT-Pad17)") (class "Default")
      (node (ref "U1") (pin "17") (pinfunction "3V3OUT_17") (pintype "output"))
    )
    (net (code "150") (name "unconnected-(U1-CTS-Pad11)") (class "Default")
      (node (ref "U1") (pin "11") (pinfunction "CTS_11") (pintype "bidirectional"))
    )
    (net (code "151") (name "unconnected-(U1-RTS-Pad3)") (class "Default")
      (node (ref "U1") (pin "3") (pinfunction "RTS_3") (pintype "bidirectional"))
    )
    (net (code "152") (name "unconnected-(U4-AIO0-Pad9)") (class "Default")
      (node (ref "U4") (pin "9") (pinfunction "AIO0_9") (pintype "bidirectional"))
    )
    (net (code "153") (name "unconnected-(U4-AIO1-Pad10)") (class "Default")
      (node (ref "U4") (pin "10") (pinfunction "AIO1_10") (pintype "bidirectional"))
    )
    (net (code "154") (name "unconnected-(U4-CLK-Pad19)") (class "Default")
      (node (ref "U4") (pin "19") (pinfunction "CLK_19") (pintype "bidirectional"))
    )
    (net (code "155") (name "unconnected-(U4-CSB-Pad16)") (class "Default")
      (node (ref "U4") (pin "16") (pinfunction "CSB_16") (pintype "bidirectional"))
    )
    (net (code "156") (name "unconnected-(U4-CTS-Pad3)") (class "Default")
      (node (ref "U4") (pin "3") (pinfunction "CTS_3") (pintype "bidirectional"))
    )
    (net (code "157") (name "unconnected-(U4-MISO-Pad18)") (class "Default")
      (node (ref "U4") (pin "18") (pinfunction "MISO_18") (pintype "bidirectional"))
    )
    (net (code "158") (name "unconnected-(U4-MOSI-Pad17)") (class "Default")
      (node (ref "U4") (pin "17") (pinfunction "MOSI_17") (pintype "bidirectional"))
    )
    (net (code "159") (name "unconnected-(U4-NC-Pad14)") (class "Default")
      (node (ref "U4") (pin "14") (pinfunction "NC_14") (pintype "bidirectional"))
    )
    (net (code "160") (name "unconnected-(U4-PCM_CLK-Pad5)") (class "Default")
      (node (ref "U4") (pin "5") (pinfunction "PCM_CLK_5") (pintype "bidirectional"))
    )
    (net (code "161") (name "unconnected-(U4-PCM_IN-Pad7)") (class "Default")
      (node (ref "U4") (pin "7") (pinfunction "PCM_IN_7") (pintype "bidirectional"))
    )
    (net (code "162") (name "unconnected-(U4-PCM_OUT-Pad6)") (class "Default")
      (node (ref "U4") (pin "6") (pinfunction "PCM_OUT_6") (pintype "bidirectional"))
    )
    (net (code "163") (name "unconnected-(U4-PCN_SYNC-Pad8)") (class "Default")
      (node (ref "U4") (pin "8") (pinfunction "PCN_SYNC_8") (pintype "bidirectional"))
    )
    (net (code "164") (name "unconnected-(U4-PIO0-Pad23)") (class "Default")
      (node (ref "U4") (pin "23") (pinfunction "PIO0_23") (pintype "bidirectional"))
    )
    (net (code "165") (name "unconnected-(U4-PIO1-Pad24)") (class "Default")
      (node (ref "U4") (pin "24") (pinfunction "PIO1_24") (pintype "bidirectional"))
    )
    (net (code "166") (name "unconnected-(U4-PIO2-Pad25)") (class "Default")
      (node (ref "U4") (pin "25") (pinfunction "PIO2_25") (pintype "bidirectional"))
    )
    (net (code "167") (name "unconnected-(U4-PIO3-Pad26)") (class "Default")
      (node (ref "U4") (pin "26") (pinfunction "PIO3_26") (pintype "bidirectional"))
    )
    (net (code "168") (name "unconnected-(U4-PIO4-Pad27)") (class "Default")
      (node (ref "U4") (pin "27") (pinfunction "PIO4_27") (pintype "bidirectional"))
    )
    (net (code "169") (name "unconnected-(U4-PIO5-Pad28)") (class "Default")
      (node (ref "U4") (pin "28") (pinfunction "PIO5_28") (pintype "bidirectional"))
    )
    (net (code "170") (name "unconnected-(U4-PIO6-Pad29)") (class "Default")
      (node (ref "U4") (pin "29") (pinfunction "PIO6_29") (pintype "bidirectional"))
    )
    (net (code "171") (name "unconnected-(U4-PIO7-Pad30)") (class "Default")
      (node (ref "U4") (pin "30") (pinfunction "PIO7_30") (pintype "bidirectional"))
    )
    (net (code "172") (name "unconnected-(U4-PIO8-Pad31)") (class "Default")
      (node (ref "U4") (pin "31") (pinfunction "PIO8_31") (pintype "bidirectional"))
    )
    (net (code "173") (name "unconnected-(U4-PIO9-Pad32)") (class "Default")
      (node (ref "U4") (pin "32") (pinfunction "PIO9_32") (pintype "bidirectional"))
    )
    (net (code "174") (name "unconnected-(U4-PIO10-Pad33)") (class "Default")
      (node (ref "U4") (pin "33") (pinfunction "PIO10_33") (pintype "bidirectional"))
    )
    (net (code "175") (name "unconnected-(U4-RST-Pad11)") (class "Default")
      (node (ref "U4") (pin "11") (pinfunction "RST_11") (pintype "bidirectional"))
    )
    (net (code "176") (name "unconnected-(U4-RTS-Pad4)") (class "Default")
      (node (ref "U4") (pin "4") (pinfunction "RTS_4") (pintype "bidirectional"))
    )
    (net (code "177") (name "unconnected-(U4-VBUSD+-Pad20)") (class "Default")
      (node (ref "U4") (pin "20") (pinfunction "VBUSD+_20") (pintype "bidirectional"))
    )
    (net (code "178") (name "unconnected-(U4-VBUSD--Pad15)") (class "Default")
      (node (ref "U4") (pin "15") (pinfunction "VBUSD-_15") (pintype "bidirectional"))
    )
    (net (code "179") (name "unconnected-(U7-NC-PadP$5)") (class "Default")
      (node (ref "U7") (pin "P$5") (pinfunction "NC_P$5") (pintype "bidirectional"))
    )
    (net (code "180") (name "unconnected-(U8-FAULT-PadP$4)") (class "Default")
      (node (ref "U8") (pin "P$4") (pinfunction "FAULT_P$4") (pintype "bidirectional"))
    )
    (net (code "181") (name "unconnected-(U16B-OUT-Pad7)") (class "Default")
      (node (ref "U16") (pin "7") (pinfunction "OUT_7") (pintype "output"))
    )
    (net (code "182") (name "unconnected-(U17-NC-Pad1)") (class "Default")
      (node (ref "U17") (pin "1") (pinfunction "NC_1") (pintype "bidirectional"))
    )
  )
)
